# M868H.net
KiCad netlist of a schematic drawn in EAGLE
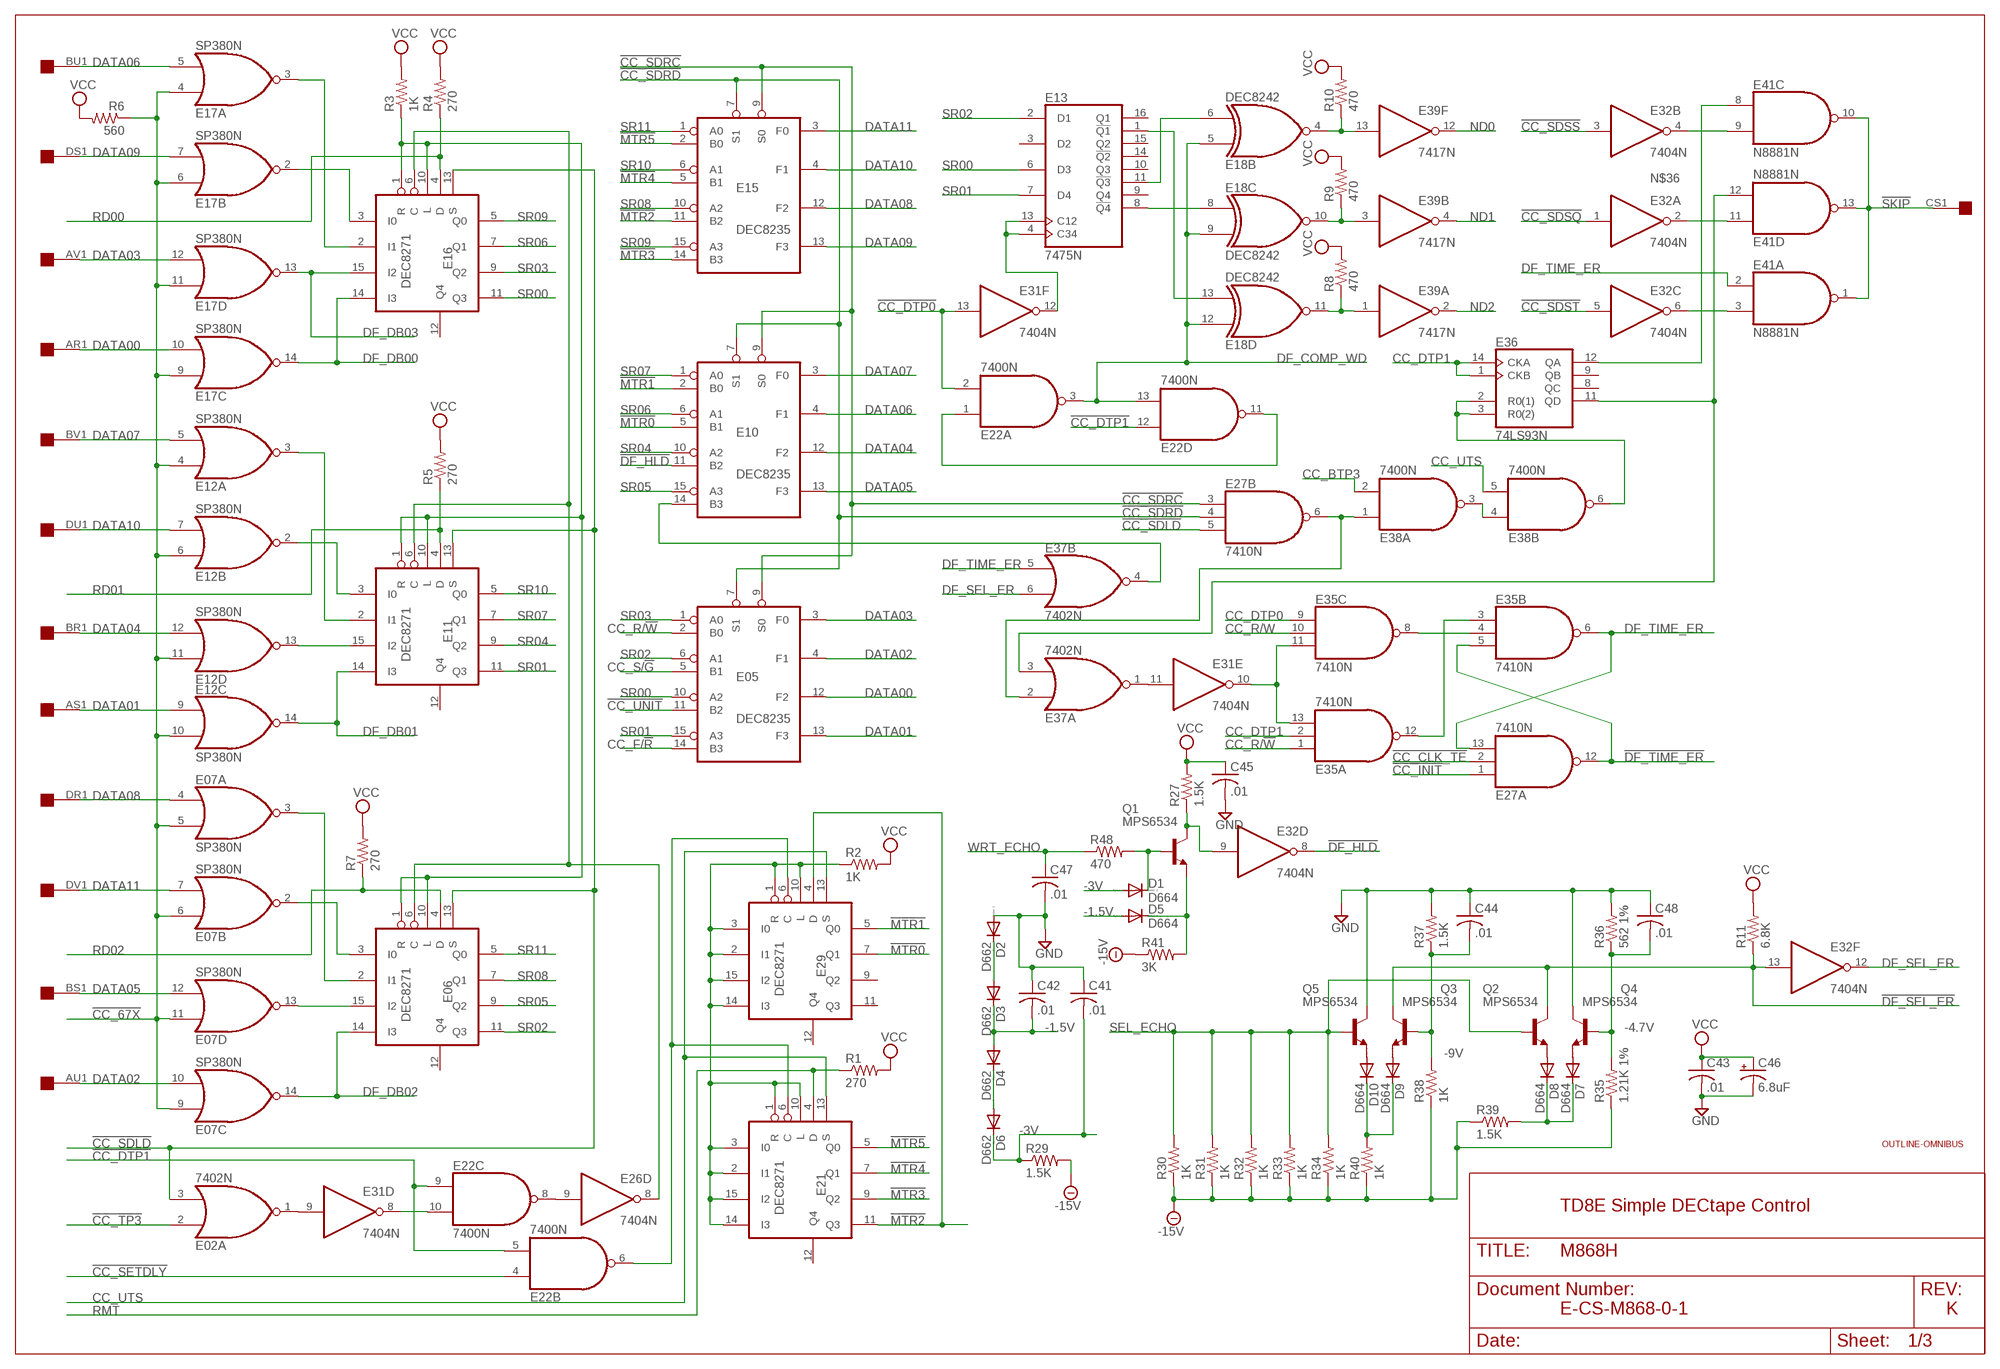
[diagram p0: schematic, sheet 1]
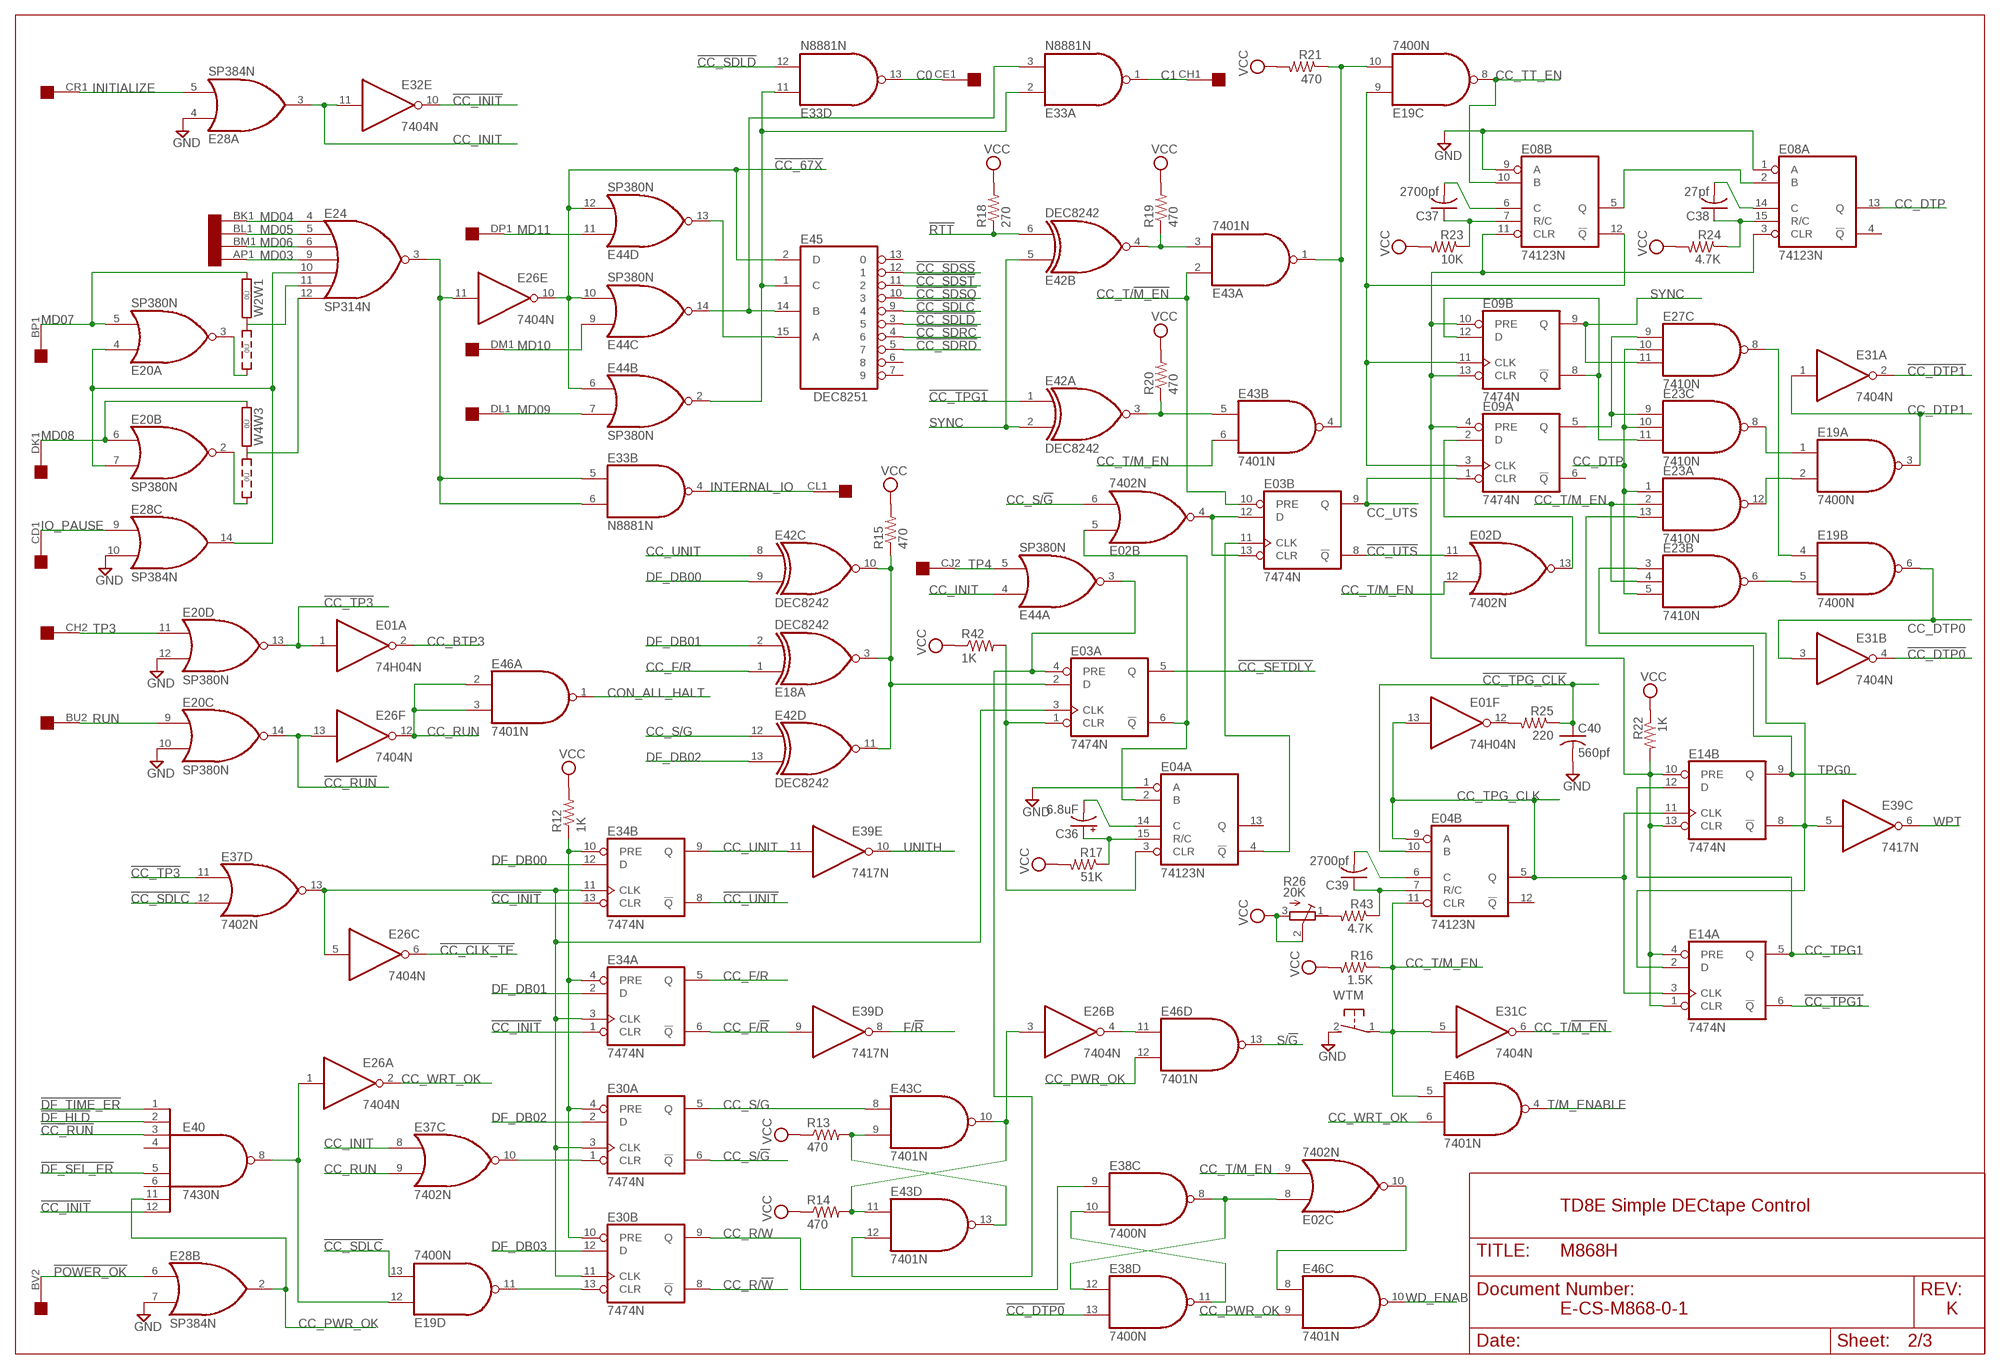
[diagram p1: schematic, sheet 2]
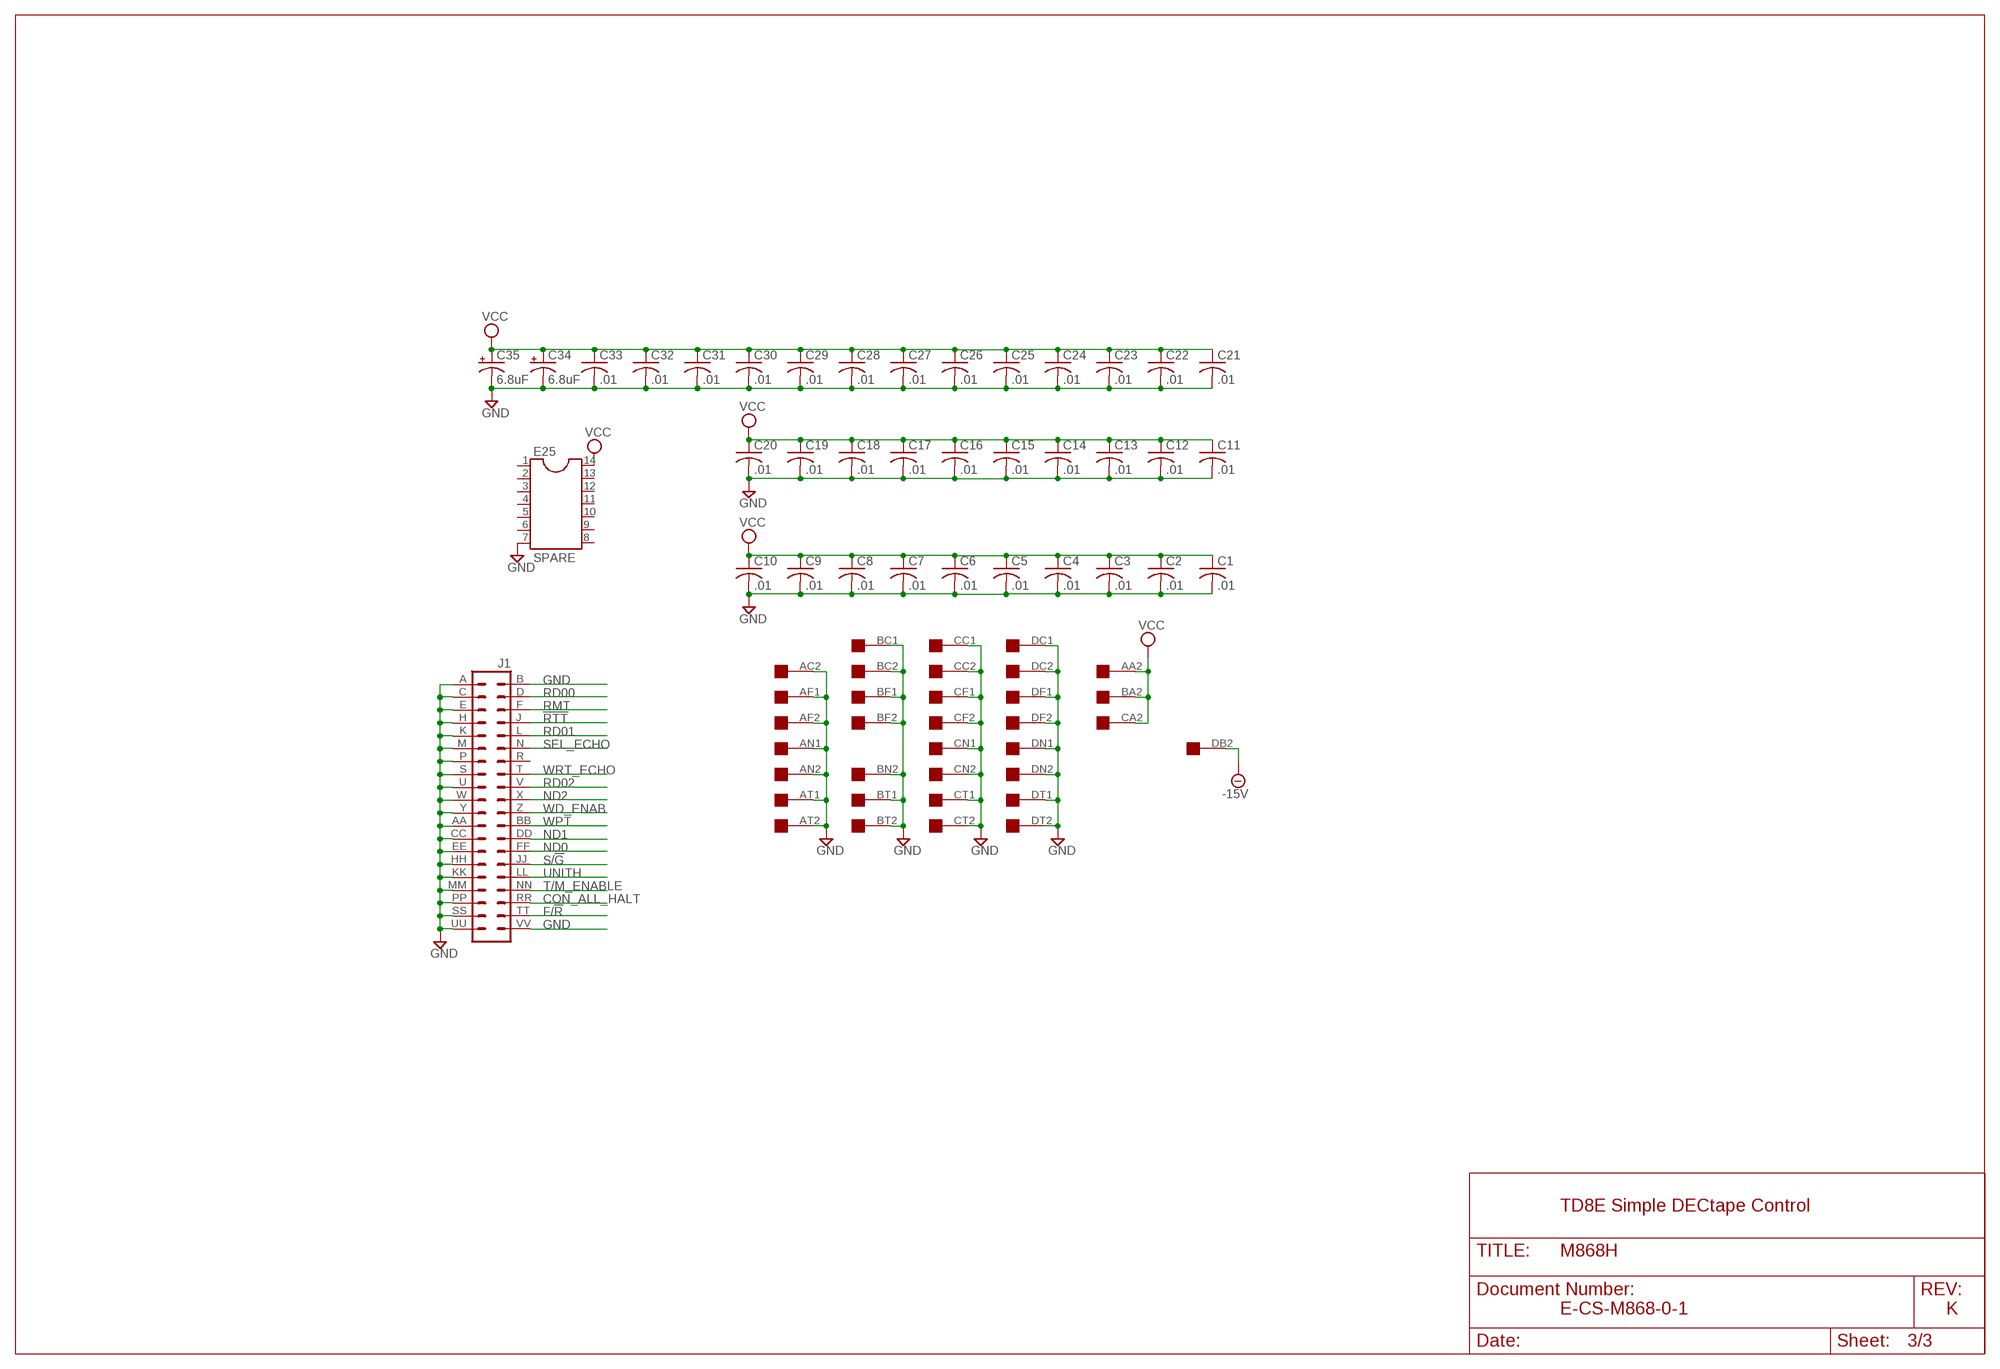
[diagram p2: schematic, sheet 3]

(export (version "E")
  (design (tool "Eeschema 10.0.6"))
  (components
    (comp (ref "C36")
      (value "6.8uF")
      (footprint "eagle-import:E12-8")
      (libsource (lib "eagle-import") (part "CPOL-USE20-8AXIAL"))
    )
    (comp (ref "C37")
      (value "2700pf")
      (footprint "eagle-import:C102-043X133")
      (libsource (lib "eagle-import") (part "C-US102-043X133"))
    )
    (comp (ref "C38")
      (value "27pf")
      (footprint "eagle-import:C050-025X075")
      (libsource (lib "eagle-import") (part "C-US050-025X075"))
    )
    (comp (ref "C39")
      (value "2700pf")
      (footprint "eagle-import:C102-043X133")
      (libsource (lib "eagle-import") (part "C-US102-043X133"))
    )
    (comp (ref "C40")
      (value "560pf")
      (footprint "eagle-import:C075-032X103")
      (libsource (lib "eagle-import") (part "C-US075-032X103"))
    )
    (comp (ref "E01")
      (value "74H04N")
      (footprint "eagle-import:DIL14")
      (libsource (lib "eagle-import") (part "7404NS"))
    )
    (comp (ref "E02")
      (value "7402N")
      (footprint "eagle-import:DIL14")
      (libsource (lib "eagle-import") (part "7402N"))
    )
    (comp (ref "E03")
      (value "7474N")
      (footprint "eagle-import:DIL14")
      (libsource (lib "eagle-import") (part "7474NS"))
    )
    (comp (ref "E04")
      (value "74123N")
      (footprint "eagle-import:DIL16")
      (libsource (lib "eagle-import") (part "74123N"))
    )
    (comp (ref "E08")
      (value "74123N")
      (footprint "eagle-import:DIL16")
      (libsource (lib "eagle-import") (part "74123N"))
    )
    (comp (ref "E09")
      (value "7474N")
      (footprint "eagle-import:DIL14")
      (libsource (lib "eagle-import") (part "7474NS"))
    )
    (comp (ref "E14")
      (value "7474N")
      (footprint "eagle-import:DIL14")
      (libsource (lib "eagle-import") (part "7474NS"))
    )
    (comp (ref "E18")
      (value "DEC8242")
      (footprint "eagle-import:DIL14")
      (libsource (lib "eagle-import") (part "74266NLS"))
    )
    (comp (ref "E19")
      (value "7400N")
      (footprint "eagle-import:DIL14")
      (libsource (lib "eagle-import") (part "7400N"))
    )
    (comp (ref "E20")
      (value "SP380N")
      (footprint "eagle-import:DIL14")
      (libsource (lib "eagle-import") (part "SP380N"))
    )
    (comp (ref "E23")
      (value "7410N")
      (footprint "eagle-import:DIL14")
      (libsource (lib "eagle-import") (part "7410N"))
    )
    (comp (ref "E24")
      (value "SP314N")
      (footprint "eagle-import:DIL14")
      (libsource (lib "eagle-import") (part "SP314N"))
    )
    (comp (ref "E26")
      (value "7404N")
      (footprint "eagle-import:DIL14")
      (libsource (lib "eagle-import") (part "7404N"))
    )
    (comp (ref "E27")
      (value "7410N")
      (footprint "eagle-import:DIL14")
      (libsource (lib "eagle-import") (part "7410N"))
    )
    (comp (ref "E28")
      (value "SP384N")
      (footprint "eagle-import:DIL14")
      (libsource (lib "eagle-import") (part "SP384N"))
    )
    (comp (ref "E30")
      (value "7474N")
      (footprint "eagle-import:DIL14")
      (libsource (lib "eagle-import") (part "7474NS"))
    )
    (comp (ref "E31")
      (value "7404N")
      (footprint "eagle-import:DIL14")
      (libsource (lib "eagle-import") (part "7404N"))
    )
    (comp (ref "E32")
      (value "7404N")
      (footprint "eagle-import:DIL14")
      (libsource (lib "eagle-import") (part "7404N"))
    )
    (comp (ref "E33")
      (value "N8881N")
      (footprint "eagle-import:DIL14")
      (libsource (lib "eagle-import") (part "N8881N"))
    )
    (comp (ref "E34")
      (value "7474N")
      (footprint "eagle-import:DIL14")
      (libsource (lib "eagle-import") (part "7474NS"))
    )
    (comp (ref "E37")
      (value "7402N")
      (footprint "eagle-import:DIL14")
      (libsource (lib "eagle-import") (part "7402N"))
    )
    (comp (ref "E38")
      (value "7400N")
      (footprint "eagle-import:DIL14")
      (libsource (lib "eagle-import") (part "7400N"))
    )
    (comp (ref "E39")
      (value "7417N")
      (footprint "eagle-import:DIL14")
      (libsource (lib "eagle-import") (part "7417N"))
    )
    (comp (ref "E40")
      (value "7430N")
      (footprint "eagle-import:DIL14")
      (libsource (lib "eagle-import") (part "7430N"))
    )
    (comp (ref "E42")
      (value "DEC8242")
      (footprint "eagle-import:DIL14")
      (libsource (lib "eagle-import") (part "74266NLS"))
    )
    (comp (ref "E43")
      (value "7401N")
      (footprint "eagle-import:DIL14")
      (libsource (lib "eagle-import") (part "7401NLS"))
    )
    (comp (ref "E44")
      (value "SP380N")
      (footprint "eagle-import:DIL14")
      (libsource (lib "eagle-import") (part "SP380N"))
    )
    (comp (ref "E45")
      (value "DEC8251")
      (footprint "eagle-import:DIL16")
      (libsource (lib "eagle-import") (part "DEC8251"))
    )
    (comp (ref "E46")
      (value "7401N")
      (footprint "eagle-import:DIL14")
      (libsource (lib "eagle-import") (part "7401NLS"))
    )
    (comp (ref "EDGE$")
      (value "QUAD")
      (footprint "eagle-import:EDGE-CON8")
      (libsource (lib "eagle-import") (part "QUAD"))
    )
    (comp (ref "R12")
      (value "1K")
      (footprint "eagle-import:0207_10")
      (libsource (lib "eagle-import") (part "R-US_0207/10"))
    )
    (comp (ref "R13")
      (value "470")
      (footprint "eagle-import:0207_10")
      (libsource (lib "eagle-import") (part "R-US_0207/10"))
    )
    (comp (ref "R14")
      (value "470")
      (footprint "eagle-import:0207_10")
      (libsource (lib "eagle-import") (part "R-US_0207/10"))
    )
    (comp (ref "R15")
      (value "470")
      (footprint "eagle-import:0207_10")
      (libsource (lib "eagle-import") (part "R-US_0207/10"))
    )
    (comp (ref "R16")
      (value "1.5K")
      (footprint "eagle-import:0207_10")
      (libsource (lib "eagle-import") (part "R-US_0207/10"))
    )
    (comp (ref "R17")
      (value "51K")
      (footprint "eagle-import:0207_10")
      (libsource (lib "eagle-import") (part "R-US_0207/10"))
    )
    (comp (ref "R18")
      (value "270")
      (footprint "eagle-import:0207_10")
      (libsource (lib "eagle-import") (part "R-US_0207/10"))
    )
    (comp (ref "R19")
      (value "470")
      (footprint "eagle-import:0207_10")
      (libsource (lib "eagle-import") (part "R-US_0207/10"))
    )
    (comp (ref "R20")
      (value "470")
      (footprint "eagle-import:0207_10")
      (libsource (lib "eagle-import") (part "R-US_0207/10"))
    )
    (comp (ref "R21")
      (value "470")
      (footprint "eagle-import:0207_10")
      (libsource (lib "eagle-import") (part "R-US_0207/10"))
    )
    (comp (ref "R22")
      (value "1K")
      (footprint "eagle-import:0207_10")
      (libsource (lib "eagle-import") (part "R-US_0207/10"))
    )
    (comp (ref "R23")
      (value "10K")
      (footprint "eagle-import:0207_10")
      (libsource (lib "eagle-import") (part "R-US_0207/10"))
    )
    (comp (ref "R24")
      (value "4.7K")
      (footprint "eagle-import:0207_10")
      (libsource (lib "eagle-import") (part "R-US_0207/10"))
    )
    (comp (ref "R25")
      (value "220")
      (footprint "eagle-import:0207_10")
      (libsource (lib "eagle-import") (part "R-US_0207/10"))
    )
    (comp (ref "R26")
      (value "20K")
      (footprint "eagle-import:3006Y")
      (libsource (lib "eagle-import") (part "275P"))
    )
    (comp (ref "R42")
      (value "1K")
      (footprint "eagle-import:0207_10")
      (libsource (lib "eagle-import") (part "R-US_0207/10"))
    )
    (comp (ref "R43")
      (value "4.7K")
      (footprint "eagle-import:0207_10")
      (libsource (lib "eagle-import") (part "R-US_0207/10"))
    )
    (comp (ref "W2W1")
      (value "0R2")
      (footprint "eagle-import:0R2_10")
      (libsource (lib "eagle-import") (part "0R2"))
    )
    (comp (ref "W4W3")
      (value "0R2")
      (footprint "eagle-import:0R2_10")
      (libsource (lib "eagle-import") (part "0R2"))
    )
    (comp (ref "WTM")
      (value "31-XX")
      (footprint "eagle-import:B3F-31XX")
      (fields (field (name "MPN") "B3F-3100"))
      (libsource (lib "eagle-import") (part "31-XX"))
    )
    (comp (ref "C1")
      (value ".01")
      (footprint "eagle-import:C050-025X075")
      (libsource (lib "eagle-import") (part "C-US050-025X075"))
    )
    (comp (ref "C2")
      (value ".01")
      (footprint "eagle-import:C050-025X075")
      (libsource (lib "eagle-import") (part "C-US050-025X075"))
    )
    (comp (ref "C3")
      (value ".01")
      (footprint "eagle-import:C050-025X075")
      (libsource (lib "eagle-import") (part "C-US050-025X075"))
    )
    (comp (ref "C4")
      (value ".01")
      (footprint "eagle-import:C050-025X075")
      (libsource (lib "eagle-import") (part "C-US050-025X075"))
    )
    (comp (ref "C5")
      (value ".01")
      (footprint "eagle-import:C050-025X075")
      (libsource (lib "eagle-import") (part "C-US050-025X075"))
    )
    (comp (ref "C6")
      (value ".01")
      (footprint "eagle-import:C050-025X075")
      (libsource (lib "eagle-import") (part "C-US050-025X075"))
    )
    (comp (ref "C7")
      (value ".01")
      (footprint "eagle-import:C050-025X075")
      (libsource (lib "eagle-import") (part "C-US050-025X075"))
    )
    (comp (ref "C8")
      (value ".01")
      (footprint "eagle-import:C050-025X075")
      (libsource (lib "eagle-import") (part "C-US050-025X075"))
    )
    (comp (ref "C9")
      (value ".01")
      (footprint "eagle-import:C050-025X075")
      (libsource (lib "eagle-import") (part "C-US050-025X075"))
    )
    (comp (ref "C10")
      (value ".01")
      (footprint "eagle-import:C050-025X075")
      (libsource (lib "eagle-import") (part "C-US050-025X075"))
    )
    (comp (ref "C11")
      (value ".01")
      (footprint "eagle-import:C050-025X075")
      (libsource (lib "eagle-import") (part "C-US050-025X075"))
    )
    (comp (ref "C12")
      (value ".01")
      (footprint "eagle-import:C050-025X075")
      (libsource (lib "eagle-import") (part "C-US050-025X075"))
    )
    (comp (ref "C13")
      (value ".01")
      (footprint "eagle-import:C050-025X075")
      (libsource (lib "eagle-import") (part "C-US050-025X075"))
    )
    (comp (ref "C14")
      (value ".01")
      (footprint "eagle-import:C050-025X075")
      (libsource (lib "eagle-import") (part "C-US050-025X075"))
    )
    (comp (ref "C15")
      (value ".01")
      (footprint "eagle-import:C050-025X075")
      (libsource (lib "eagle-import") (part "C-US050-025X075"))
    )
    (comp (ref "C16")
      (value ".01")
      (footprint "eagle-import:C050-025X075")
      (libsource (lib "eagle-import") (part "C-US050-025X075"))
    )
    (comp (ref "C17")
      (value ".01")
      (footprint "eagle-import:C050-025X075")
      (libsource (lib "eagle-import") (part "C-US050-025X075"))
    )
    (comp (ref "C18")
      (value ".01")
      (footprint "eagle-import:C050-025X075")
      (libsource (lib "eagle-import") (part "C-US050-025X075"))
    )
    (comp (ref "C19")
      (value ".01")
      (footprint "eagle-import:C050-025X075")
      (libsource (lib "eagle-import") (part "C-US050-025X075"))
    )
    (comp (ref "C20")
      (value ".01")
      (footprint "eagle-import:C050-025X075")
      (libsource (lib "eagle-import") (part "C-US050-025X075"))
    )
    (comp (ref "C21")
      (value ".01")
      (footprint "eagle-import:C050-025X075")
      (libsource (lib "eagle-import") (part "C-US050-025X075"))
    )
    (comp (ref "C22")
      (value ".01")
      (footprint "eagle-import:C050-025X075")
      (libsource (lib "eagle-import") (part "C-US050-025X075"))
    )
    (comp (ref "C23")
      (value ".01")
      (footprint "eagle-import:C050-025X075")
      (libsource (lib "eagle-import") (part "C-US050-025X075"))
    )
    (comp (ref "C24")
      (value ".01")
      (footprint "eagle-import:C050-025X075")
      (libsource (lib "eagle-import") (part "C-US050-025X075"))
    )
    (comp (ref "C25")
      (value ".01")
      (footprint "eagle-import:C050-025X075")
      (libsource (lib "eagle-import") (part "C-US050-025X075"))
    )
    (comp (ref "C26")
      (value ".01")
      (footprint "eagle-import:C050-025X075")
      (libsource (lib "eagle-import") (part "C-US050-025X075"))
    )
    (comp (ref "C27")
      (value ".01")
      (footprint "eagle-import:C050-025X075")
      (libsource (lib "eagle-import") (part "C-US050-025X075"))
    )
    (comp (ref "C28")
      (value ".01")
      (footprint "eagle-import:C050-025X075")
      (libsource (lib "eagle-import") (part "C-US050-025X075"))
    )
    (comp (ref "C29")
      (value ".01")
      (footprint "eagle-import:C050-025X075")
      (libsource (lib "eagle-import") (part "C-US050-025X075"))
    )
    (comp (ref "C30")
      (value ".01")
      (footprint "eagle-import:C050-025X075")
      (libsource (lib "eagle-import") (part "C-US050-025X075"))
    )
    (comp (ref "C31")
      (value ".01")
      (footprint "eagle-import:C050-025X075")
      (libsource (lib "eagle-import") (part "C-US050-025X075"))
    )
    (comp (ref "C32")
      (value ".01")
      (footprint "eagle-import:C050-025X075")
      (libsource (lib "eagle-import") (part "C-US050-025X075"))
    )
    (comp (ref "C33")
      (value ".01")
      (footprint "eagle-import:C050-025X075")
      (libsource (lib "eagle-import") (part "C-US050-025X075"))
    )
    (comp (ref "C34")
      (value "6.8uF")
      (footprint "eagle-import:E12-8")
      (libsource (lib "eagle-import") (part "CPOL-USE20-8AXIAL"))
    )
    (comp (ref "C35")
      (value "6.8uF")
      (footprint "eagle-import:E12-8")
      (libsource (lib "eagle-import") (part "CPOL-USE20-8AXIAL"))
    )
    (comp (ref "E25")
      (value "SPARE")
      (footprint "eagle-import:DIL14")
      (libsource (lib "eagle-import") (part "DIL14"))
    )
    (comp (ref "J1")
      (value "DEC40PINH")
      (footprint "eagle-import:DEC40PINH")
      (libsource (lib "eagle-import") (part "DEC40PINH"))
    )
    (comp (ref "C41")
      (value ".01")
      (footprint "eagle-import:C050-025X075")
      (libsource (lib "eagle-import") (part "C-US050-025X075"))
    )
    (comp (ref "C42")
      (value ".01")
      (footprint "eagle-import:C050-025X075")
      (libsource (lib "eagle-import") (part "C-US050-025X075"))
    )
    (comp (ref "C43")
      (value ".01")
      (footprint "eagle-import:C050-025X075")
      (libsource (lib "eagle-import") (part "C-US050-025X075"))
    )
    (comp (ref "C44")
      (value ".01")
      (footprint "eagle-import:C050-025X075")
      (libsource (lib "eagle-import") (part "C-US050-025X075"))
    )
    (comp (ref "C45")
      (value ".01")
      (footprint "eagle-import:C050-025X075")
      (libsource (lib "eagle-import") (part "C-US050-025X075"))
    )
    (comp (ref "C46")
      (value "6.8uF")
      (footprint "eagle-import:E12-8")
      (libsource (lib "eagle-import") (part "CPOL-USE20-8AXIAL"))
    )
    (comp (ref "C47")
      (value ".01")
      (footprint "eagle-import:C050-025X075")
      (libsource (lib "eagle-import") (part "C-US050-025X075"))
    )
    (comp (ref "C48")
      (value ".01")
      (footprint "eagle-import:C050-025X075")
      (libsource (lib "eagle-import") (part "C-US050-025X075"))
    )
    (comp (ref "D1")
      (value "D664")
      (footprint "eagle-import:DO35-10")
      (libsource (lib "eagle-import") (part "1N4148DO35-10"))
    )
    (comp (ref "D2")
      (value "D662")
      (footprint "eagle-import:DO35-10")
      (libsource (lib "eagle-import") (part "1N4148DO35-10"))
    )
    (comp (ref "D3")
      (value "D662")
      (footprint "eagle-import:DO35-10")
      (libsource (lib "eagle-import") (part "1N4148DO35-10"))
    )
    (comp (ref "D4")
      (value "D662")
      (footprint "eagle-import:DO35-10")
      (libsource (lib "eagle-import") (part "1N4148DO35-10"))
    )
    (comp (ref "D5")
      (value "D664")
      (footprint "eagle-import:DO35-10")
      (libsource (lib "eagle-import") (part "1N4148DO35-10"))
    )
    (comp (ref "D6")
      (value "D662")
      (footprint "eagle-import:DO35-10")
      (libsource (lib "eagle-import") (part "1N4148DO35-10"))
    )
    (comp (ref "D7")
      (value "D664")
      (footprint "eagle-import:DO35-10")
      (libsource (lib "eagle-import") (part "1N4148DO35-10"))
    )
    (comp (ref "D8")
      (value "D664")
      (footprint "eagle-import:DO35-10")
      (libsource (lib "eagle-import") (part "1N4148DO35-10"))
    )
    (comp (ref "D9")
      (value "D664")
      (footprint "eagle-import:DO35-10")
      (libsource (lib "eagle-import") (part "1N4148DO35-10"))
    )
    (comp (ref "D10")
      (value "D664")
      (footprint "eagle-import:DO35-10")
      (libsource (lib "eagle-import") (part "1N4148DO35-10"))
    )
    (comp (ref "E05")
      (value "DEC8235")
      (footprint "eagle-import:DIL16")
      (libsource (lib "eagle-import") (part "DEC8235"))
    )
    (comp (ref "E06")
      (value "DEC8271")
      (footprint "eagle-import:DIL16")
      (libsource (lib "eagle-import") (part "DEC8271"))
    )
    (comp (ref "E07")
      (value "SP380N")
      (footprint "eagle-import:DIL14")
      (libsource (lib "eagle-import") (part "SP380N"))
    )
    (comp (ref "E10")
      (value "DEC8235")
      (footprint "eagle-import:DIL16")
      (libsource (lib "eagle-import") (part "DEC8235"))
    )
    (comp (ref "E11")
      (value "DEC8271")
      (footprint "eagle-import:DIL16")
      (libsource (lib "eagle-import") (part "DEC8271"))
    )
    (comp (ref "E12")
      (value "SP380N")
      (footprint "eagle-import:DIL14")
      (libsource (lib "eagle-import") (part "SP380N"))
    )
    (comp (ref "E13")
      (value "7475N")
      (footprint "eagle-import:DIL16")
      (libsource (lib "eagle-import") (part "7475N"))
    )
    (comp (ref "E15")
      (value "DEC8235")
      (footprint "eagle-import:DIL16")
      (libsource (lib "eagle-import") (part "DEC8235"))
    )
    (comp (ref "E16")
      (value "DEC8271")
      (footprint "eagle-import:DIL16")
      (libsource (lib "eagle-import") (part "DEC8271"))
    )
    (comp (ref "E17")
      (value "SP380N")
      (footprint "eagle-import:DIL14")
      (libsource (lib "eagle-import") (part "SP380N"))
    )
    (comp (ref "E21")
      (value "DEC8271")
      (footprint "eagle-import:DIL16")
      (libsource (lib "eagle-import") (part "DEC8271"))
    )
    (comp (ref "E22")
      (value "7400N")
      (footprint "eagle-import:DIL14")
      (libsource (lib "eagle-import") (part "7400N"))
    )
    (comp (ref "E29")
      (value "DEC8271")
      (footprint "eagle-import:DIL16")
      (libsource (lib "eagle-import") (part "DEC8271"))
    )
    (comp (ref "E35")
      (value "7410N")
      (footprint "eagle-import:DIL14")
      (libsource (lib "eagle-import") (part "7410N"))
    )
    (comp (ref "E36")
      (value "74LS93N")
      (footprint "eagle-import:DIL14")
      (libsource (lib "eagle-import") (part "7493NLS"))
    )
    (comp (ref "E41")
      (value "N8881N")
      (footprint "eagle-import:DIL14")
      (libsource (lib "eagle-import") (part "N8881N"))
    )
    (comp (ref "Q1")
      (value "MPS6534")
      (footprint "eagle-import:TO5")
      (libsource (lib "eagle-import") (part "2N2219"))
    )
    (comp (ref "Q2")
      (value "MPS6534")
      (footprint "eagle-import:TO5")
      (libsource (lib "eagle-import") (part "2N2219"))
    )
    (comp (ref "Q3")
      (value "MPS6534")
      (footprint "eagle-import:TO5")
      (libsource (lib "eagle-import") (part "2N2219"))
    )
    (comp (ref "Q4")
      (value "MPS6534")
      (footprint "eagle-import:TO5")
      (libsource (lib "eagle-import") (part "2N2219"))
    )
    (comp (ref "Q5")
      (value "MPS6534")
      (footprint "eagle-import:TO5")
      (libsource (lib "eagle-import") (part "2N2219"))
    )
    (comp (ref "R1")
      (value "270")
      (footprint "eagle-import:0207_10")
      (libsource (lib "eagle-import") (part "R-US_0207/10"))
    )
    (comp (ref "R2")
      (value "1K")
      (footprint "eagle-import:0207_10")
      (libsource (lib "eagle-import") (part "R-US_0207/10"))
    )
    (comp (ref "R3")
      (value "1K")
      (footprint "eagle-import:0207_10")
      (libsource (lib "eagle-import") (part "R-US_0207/10"))
    )
    (comp (ref "R4")
      (value "270")
      (footprint "eagle-import:0207_10")
      (libsource (lib "eagle-import") (part "R-US_0207/10"))
    )
    (comp (ref "R5")
      (value "270")
      (footprint "eagle-import:0207_10")
      (libsource (lib "eagle-import") (part "R-US_0207/10"))
    )
    (comp (ref "R6")
      (value "560")
      (footprint "eagle-import:0207_10")
      (libsource (lib "eagle-import") (part "R-US_0207/10"))
    )
    (comp (ref "R7")
      (value "270")
      (footprint "eagle-import:0207_10")
      (libsource (lib "eagle-import") (part "R-US_0207/10"))
    )
    (comp (ref "R8")
      (value "470")
      (footprint "eagle-import:0207_10")
      (libsource (lib "eagle-import") (part "R-US_0207/10"))
    )
    (comp (ref "R9")
      (value "470")
      (footprint "eagle-import:0207_10")
      (libsource (lib "eagle-import") (part "R-US_0207/10"))
    )
    (comp (ref "R10")
      (value "470")
      (footprint "eagle-import:0207_10")
      (libsource (lib "eagle-import") (part "R-US_0207/10"))
    )
    (comp (ref "R11")
      (value "6.8K")
      (footprint "eagle-import:0207_10")
      (libsource (lib "eagle-import") (part "R-US_0207/10"))
    )
    (comp (ref "R27")
      (value "1.5K")
      (footprint "eagle-import:0207_10")
      (libsource (lib "eagle-import") (part "R-US_0207/10"))
    )
    (comp (ref "R29")
      (value "1.5K")
      (footprint "eagle-import:0207_10")
      (libsource (lib "eagle-import") (part "R-US_0207/10"))
    )
    (comp (ref "R30")
      (value "1K")
      (footprint "eagle-import:0207_10")
      (libsource (lib "eagle-import") (part "R-US_0207/10"))
    )
    (comp (ref "R31")
      (value "1K")
      (footprint "eagle-import:0207_10")
      (libsource (lib "eagle-import") (part "R-US_0207/10"))
    )
    (comp (ref "R32")
      (value "1K")
      (footprint "eagle-import:0207_10")
      (libsource (lib "eagle-import") (part "R-US_0207/10"))
    )
    (comp (ref "R33")
      (value "1K")
      (footprint "eagle-import:0207_10")
      (libsource (lib "eagle-import") (part "R-US_0207/10"))
    )
    (comp (ref "R34")
      (value "1K")
      (footprint "eagle-import:0207_10")
      (libsource (lib "eagle-import") (part "R-US_0207/10"))
    )
    (comp (ref "R35")
      (value "1.21K 1%")
      (footprint "eagle-import:0207_15")
      (libsource (lib "eagle-import") (part "R-US_0207/15"))
    )
    (comp (ref "R36")
      (value "562 1%")
      (footprint "eagle-import:0207_15")
      (libsource (lib "eagle-import") (part "R-US_0207/15"))
    )
    (comp (ref "R37")
      (value "1.5K")
      (footprint "eagle-import:0207_10")
      (libsource (lib "eagle-import") (part "R-US_0207/10"))
    )
    (comp (ref "R38")
      (value "1K")
      (footprint "eagle-import:0207_10")
      (libsource (lib "eagle-import") (part "R-US_0207/10"))
    )
    (comp (ref "R39")
      (value "1.5K")
      (footprint "eagle-import:0207_10")
      (libsource (lib "eagle-import") (part "R-US_0207/10"))
    )
    (comp (ref "R40")
      (value "1K")
      (footprint "eagle-import:0207_10")
      (libsource (lib "eagle-import") (part "R-US_0207/10"))
    )
    (comp (ref "R41")
      (value "3K")
      (footprint "eagle-import:0207_10")
      (libsource (lib "eagle-import") (part "R-US_0207/10"))
    )
    (comp (ref "R48")
      (value "470")
      (footprint "eagle-import:0207_10")
      (libsource (lib "eagle-import") (part "R-US_0207/10"))
    )
    (comp (ref "U$1")
      (value "OUTLINE-OMNIBUS")
      (footprint "eagle-import:OMNIBUS")
      (libsource (lib "eagle-import") (part "OUTLINE-OMNIBUS"))
    )
  )
  (nets
    (net (code "1") (name "-1.5V") (class "Default")
      (node (ref "C42") (pin "2") (pinfunction "2_2") (pintype "passive"))
      (node (ref "D3") (pin "C") (pinfunction "C_C") (pintype "passive"))
      (node (ref "D4") (pin "A") (pinfunction "A_A") (pintype "passive"))
      (node (ref "D5") (pin "A") (pinfunction "A_A") (pintype "passive"))
    )
    (net (code "2") (name "-3V") (class "Default")
      (node (ref "C41") (pin "2") (pinfunction "2_2") (pintype "passive"))
      (node (ref "D1") (pin "A") (pinfunction "A_A") (pintype "passive"))
      (node (ref "D6") (pin "C") (pinfunction "C_C") (pintype "passive"))
      (node (ref "R29") (pin "1") (pinfunction "1_1") (pintype "passive"))
    )
    (net (code "3") (name "-4.7V") (class "Default")
      (node (ref "C48") (pin "2") (pinfunction "2_2") (pintype "passive"))
      (node (ref "Q4") (pin "2") (pinfunction "B_2") (pintype "passive"))
      (node (ref "R35") (pin "2") (pinfunction "2_2") (pintype "passive"))
      (node (ref "R36") (pin "1") (pinfunction "1_1") (pintype "passive"))
    )
    (net (code "4") (name "-9V") (class "Default")
      (node (ref "C44") (pin "2") (pinfunction "2_2") (pintype "passive"))
      (node (ref "Q3") (pin "2") (pinfunction "B_2") (pintype "passive"))
      (node (ref "R37") (pin "1") (pinfunction "1_1") (pintype "passive"))
      (node (ref "R38") (pin "2") (pinfunction "2_2") (pintype "passive"))
    )
    (net (code "5") (name "-15V") (class "Default")
      (node (ref "EDGE$") (pin "DB2") (pinfunction "1_DB2") (pintype "bidirectional"))
      (node (ref "R29") (pin "2") (pinfunction "2_2") (pintype "passive"))
      (node (ref "R30") (pin "1") (pinfunction "1_1") (pintype "passive"))
      (node (ref "R31") (pin "1") (pinfunction "1_1") (pintype "passive"))
      (node (ref "R32") (pin "1") (pinfunction "1_1") (pintype "passive"))
      (node (ref "R33") (pin "1") (pinfunction "1_1") (pintype "passive"))
      (node (ref "R34") (pin "1") (pinfunction "1_1") (pintype "passive"))
      (node (ref "R35") (pin "1") (pinfunction "1_1") (pintype "passive"))
      (node (ref "R38") (pin "1") (pinfunction "1_1") (pintype "passive"))
      (node (ref "R39") (pin "1") (pinfunction "1_1") (pintype "passive"))
      (node (ref "R40") (pin "1") (pinfunction "1_1") (pintype "passive"))
      (node (ref "R41") (pin "1") (pinfunction "1_1") (pintype "passive"))
    )
    (net (code "6") (name "C0") (class "Default")
      (node (ref "E33") (pin "13") (pinfunction "O_13") (pintype "open_collector"))
      (node (ref "EDGE$") (pin "CE1") (pinfunction "1_CE1") (pintype "bidirectional"))
    )
    (net (code "7") (name "C1") (class "Default")
      (node (ref "E33") (pin "1") (pinfunction "O_1") (pintype "open_collector"))
      (node (ref "EDGE$") (pin "CH1") (pinfunction "1_CH1") (pintype "bidirectional"))
    )
    (net (code "8") (name "CC_BTP3") (class "Default")
      (node (ref "E01") (pin "2") (pinfunction "O_2") (pintype "output"))
      (node (ref "E38") (pin "2") (pinfunction "I1_2") (pintype "input"))
    )
    (net (code "9") (name "CC_DTP") (class "Default")
      (node (ref "E08") (pin "13") (pinfunction "Q_13") (pintype "output"))
      (node (ref "E23") (pin "1") (pinfunction "I0_1") (pintype "input"))
      (node (ref "E23") (pin "10") (pinfunction "I1_10") (pintype "input"))
      (node (ref "E23") (pin "5") (pinfunction "I2_5") (pintype "input"))
      (node (ref "E27") (pin "10") (pinfunction "I1_10") (pintype "input"))
    )
    (net (code "10") (name "CC_DTP0") (class "Default")
      (node (ref "E19") (pin "6") (pinfunction "O_6") (pintype "output"))
      (node (ref "E31") (pin "3") (pinfunction "I_3") (pintype "input"))
      (node (ref "E35") (pin "9") (pinfunction "I0_9") (pintype "input"))
    )
    (net (code "11") (name "CC_DTP1") (class "Default")
      (node (ref "E19") (pin "3") (pinfunction "O_3") (pintype "output"))
      (node (ref "E31") (pin "1") (pinfunction "I_1") (pintype "input"))
      (node (ref "E35") (pin "2") (pinfunction "I1_2") (pintype "input"))
      (node (ref "E36") (pin "1") (pinfunction "CKB_1") (pintype "input"))
      (node (ref "E36") (pin "14") (pinfunction "CKA_14") (pintype "input"))
    )
    (net (code "12") (name "CC_F{slash}R") (class "Default")
      (node (ref "E18") (pin "1") (pinfunction "I0_1") (pintype "input"))
      (node (ref "E34") (pin "5") (pinfunction "Q_5") (pintype "output"))
    )
    (net (code "13") (name "CC_F{slash}~{R}") (class "Default")
      (node (ref "E05") (pin "14") (pinfunction "B3_14") (pintype "input"))
      (node (ref "E34") (pin "6") (pinfunction "~{Q}_6") (pintype "output"))
      (node (ref "E39") (pin "9") (pinfunction "I_9") (pintype "input"))
    )
    (net (code "14") (name "CC_INIT") (class "Default")
      (node (ref "E28") (pin "3") (pinfunction "O_3") (pintype "output"))
      (node (ref "E32") (pin "11") (pinfunction "I_11") (pintype "input"))
      (node (ref "E37") (pin "8") (pinfunction "I0_8") (pintype "input"))
      (node (ref "E44") (pin "4") (pinfunction "I0_4") (pintype "input"))
    )
    (net (code "15") (name "CC_PWR_OK") (class "Default")
      (node (ref "E28") (pin "2") (pinfunction "O_2") (pintype "output"))
      (node (ref "E40") (pin "11") (pinfunction "I6_11") (pintype "input"))
      (node (ref "E46") (pin "12") (pinfunction "I1_12") (pintype "input"))
      (node (ref "E46") (pin "9") (pinfunction "I1_9") (pintype "input"))
    )
    (net (code "16") (name "CC_RUN") (class "Default")
      (node (ref "E26") (pin "12") (pinfunction "O_12") (pintype "output"))
      (node (ref "E37") (pin "9") (pinfunction "I1_9") (pintype "input"))
      (node (ref "E46") (pin "2") (pinfunction "I0_2") (pintype "input"))
      (node (ref "E46") (pin "3") (pinfunction "I1_3") (pintype "input"))
    )
    (net (code "17") (name "CC_R{slash}W") (class "Default")
      (node (ref "E30") (pin "9") (pinfunction "Q_9") (pintype "output"))
      (node (ref "E35") (pin "10") (pinfunction "I1_10") (pintype "input"))
      (node (ref "E38") (pin "9") (pinfunction "I0_9") (pintype "input"))
    )
    (net (code "18") (name "CC_R{slash}~{W}") (class "Default")
      (node (ref "E05") (pin "2") (pinfunction "B0_2") (pintype "input"))
      (node (ref "E30") (pin "8") (pinfunction "~{Q}_8") (pintype "output"))
      (node (ref "E35") (pin "1") (pinfunction "I0_1") (pintype "input"))
    )
    (net (code "19") (name "CC_S{slash}G") (class "Default")
      (node (ref "E30") (pin "5") (pinfunction "Q_5") (pintype "output"))
      (node (ref "E42") (pin "12") (pinfunction "I0_12") (pintype "input"))
      (node (ref "E43") (pin "8") (pinfunction "I0_8") (pintype "input"))
    )
    (net (code "20") (name "CC_S{slash}~{G}") (class "Default")
      (node (ref "E02") (pin "6") (pinfunction "I1_6") (pintype "input"))
      (node (ref "E05") (pin "5") (pinfunction "B1_5") (pintype "input"))
      (node (ref "E30") (pin "6") (pinfunction "~{Q}_6") (pintype "output"))
    )
    (net (code "21") (name "CC_TPG1") (class "Default")
      (node (ref "E14") (pin "12") (pinfunction "D_12") (pintype "input"))
      (node (ref "E14") (pin "5") (pinfunction "Q_5") (pintype "output"))
    )
    (net (code "22") (name "CC_TPG_CLK") (class "Default")
      (node (ref "E01") (pin "13") (pinfunction "I_13") (pintype "input"))
      (node (ref "E04") (pin "5") (pinfunction "Q_5") (pintype "output"))
      (node (ref "E04") (pin "9") (pinfunction "A_9") (pintype "input"))
      (node (ref "E14") (pin "11") (pinfunction "CLK_11") (pintype "input"))
      (node (ref "E14") (pin "3") (pinfunction "CLK_3") (pintype "input"))
    )
    (net (code "23") (name "CC_TT_EN") (class "Default")
      (node (ref "E08") (pin "10") (pinfunction "B_10") (pintype "input"))
      (node (ref "E19") (pin "8") (pinfunction "O_8") (pintype "output"))
    )
    (net (code "24") (name "CC_T{slash}M_EN") (class "Default")
      (node (ref "E02") (pin "12") (pinfunction "I1_12") (pintype "input"))
      (node (ref "E02") (pin "9") (pinfunction "I1_9") (pintype "input"))
      (node (ref "E04") (pin "11") (pinfunction "CLR_11") (pintype "input"))
      (node (ref "E23") (pin "2") (pinfunction "I1_2") (pintype "input"))
      (node (ref "E23") (pin "4") (pinfunction "I1_4") (pintype "input"))
      (node (ref "E31") (pin "5") (pinfunction "I_5") (pintype "input"))
      (node (ref "E43") (pin "6") (pinfunction "I1_6") (pintype "input"))
      (node (ref "E46") (pin "5") (pinfunction "I0_5") (pintype "input"))
      (node (ref "R16") (pin "1") (pinfunction "1_1") (pintype "passive"))
      (node (ref "WTM") (pin "1") (pinfunction "P_1") (pintype "passive"))
    )
    (net (code "25") (name "CC_T{slash}~{M_EN}") (class "Default")
      (node (ref "E03") (pin "10") (pinfunction "PRE_10") (pintype "input"))
      (node (ref "E31") (pin "6") (pinfunction "O_6") (pintype "output"))
      (node (ref "E43") (pin "2") (pinfunction "I0_2") (pintype "input"))
    )
    (net (code "26") (name "CC_UNIT") (class "Default")
      (node (ref "E34") (pin "9") (pinfunction "Q_9") (pintype "output"))
      (node (ref "E39") (pin "11") (pinfunction "I_11") (pintype "input"))
      (node (ref "E42") (pin "8") (pinfunction "I0_8") (pintype "input"))
    )
    (net (code "27") (name "CC_UTS") (class "Default")
      (node (ref "E03") (pin "9") (pinfunction "Q_9") (pintype "output"))
      (node (ref "E09") (pin "1") (pinfunction "CLR_1") (pintype "input"))
      (node (ref "E21") (pin "13") (pinfunction "S_13") (pintype "input"))
      (node (ref "E29") (pin "13") (pinfunction "S_13") (pintype "input"))
      (node (ref "E38") (pin "5") (pinfunction "I1_5") (pintype "input"))
    )
    (net (code "28") (name "CC_WRT_OK") (class "Default")
      (node (ref "E26") (pin "2") (pinfunction "O_2") (pintype "output"))
      (node (ref "E46") (pin "6") (pinfunction "I1_6") (pintype "input"))
    )
    (net (code "29") (name "CON_ALL_HALT") (class "Default")
      (node (ref "E46") (pin "1") (pinfunction "O_1") (pintype "open_collector"))
      (node (ref "J1") (pin "RR") (pinfunction "36_RR") (pintype "bidirectional"))
    )
    (net (code "30") (name "DATA00") (class "Default")
      (node (ref "E05") (pin "12") (pinfunction "F2_12") (pintype "open_collector"))
      (node (ref "E17") (pin "10") (pinfunction "I1_10") (pintype "input"))
      (node (ref "EDGE$") (pin "AR1") (pinfunction "1_AR1") (pintype "bidirectional"))
    )
    (net (code "31") (name "DATA01") (class "Default")
      (node (ref "E05") (pin "13") (pinfunction "F3_13") (pintype "open_collector"))
      (node (ref "E12") (pin "9") (pinfunction "I0_9") (pintype "input"))
      (node (ref "EDGE$") (pin "AS1") (pinfunction "1_AS1") (pintype "bidirectional"))
    )
    (net (code "32") (name "DATA02") (class "Default")
      (node (ref "E05") (pin "4") (pinfunction "F1_4") (pintype "open_collector"))
      (node (ref "E07") (pin "10") (pinfunction "I1_10") (pintype "input"))
      (node (ref "EDGE$") (pin "AU1") (pinfunction "1_AU1") (pintype "bidirectional"))
    )
    (net (code "33") (name "DATA03") (class "Default")
      (node (ref "E05") (pin "3") (pinfunction "F0_3") (pintype "open_collector"))
      (node (ref "E17") (pin "12") (pinfunction "I1_12") (pintype "input"))
      (node (ref "EDGE$") (pin "AV1") (pinfunction "1_AV1") (pintype "bidirectional"))
    )
    (net (code "34") (name "DATA04") (class "Default")
      (node (ref "E10") (pin "12") (pinfunction "F2_12") (pintype "open_collector"))
      (node (ref "E12") (pin "12") (pinfunction "I1_12") (pintype "input"))
      (node (ref "EDGE$") (pin "BR1") (pinfunction "1_BR1") (pintype "bidirectional"))
    )
    (net (code "35") (name "DATA05") (class "Default")
      (node (ref "E07") (pin "12") (pinfunction "I1_12") (pintype "input"))
      (node (ref "E10") (pin "13") (pinfunction "F3_13") (pintype "open_collector"))
      (node (ref "EDGE$") (pin "BS1") (pinfunction "1_BS1") (pintype "bidirectional"))
    )
    (net (code "36") (name "DATA06") (class "Default")
      (node (ref "E10") (pin "4") (pinfunction "F1_4") (pintype "open_collector"))
      (node (ref "E17") (pin "5") (pinfunction "I1_5") (pintype "input"))
      (node (ref "EDGE$") (pin "BU1") (pinfunction "1_BU1") (pintype "bidirectional"))
    )
    (net (code "37") (name "DATA07") (class "Default")
      (node (ref "E10") (pin "3") (pinfunction "F0_3") (pintype "open_collector"))
      (node (ref "E12") (pin "5") (pinfunction "I1_5") (pintype "input"))
      (node (ref "EDGE$") (pin "BV1") (pinfunction "1_BV1") (pintype "bidirectional"))
    )
    (net (code "38") (name "DATA08") (class "Default")
      (node (ref "E07") (pin "4") (pinfunction "I0_4") (pintype "input"))
      (node (ref "E15") (pin "12") (pinfunction "F2_12") (pintype "open_collector"))
      (node (ref "EDGE$") (pin "DR1") (pinfunction "1_DR1") (pintype "bidirectional"))
    )
    (net (code "39") (name "DATA09") (class "Default")
      (node (ref "E15") (pin "13") (pinfunction "F3_13") (pintype "open_collector"))
      (node (ref "E17") (pin "7") (pinfunction "I1_7") (pintype "input"))
      (node (ref "EDGE$") (pin "DS1") (pinfunction "1_DS1") (pintype "bidirectional"))
    )
    (net (code "40") (name "DATA10") (class "Default")
      (node (ref "E12") (pin "7") (pinfunction "I1_7") (pintype "input"))
      (node (ref "E15") (pin "4") (pinfunction "F1_4") (pintype "open_collector"))
      (node (ref "EDGE$") (pin "DU1") (pinfunction "1_DU1") (pintype "bidirectional"))
    )
    (net (code "41") (name "DATA11") (class "Default")
      (node (ref "E07") (pin "7") (pinfunction "I1_7") (pintype "input"))
      (node (ref "E15") (pin "3") (pinfunction "F0_3") (pintype "open_collector"))
      (node (ref "EDGE$") (pin "DV1") (pinfunction "1_DV1") (pintype "bidirectional"))
    )
    (net (code "42") (name "DF_COMP_WD") (class "Default")
      (node (ref "E18") (pin "12") (pinfunction "I0_12") (pintype "input"))
      (node (ref "E18") (pin "5") (pinfunction "I0_5") (pintype "input"))
      (node (ref "E18") (pin "9") (pinfunction "I1_9") (pintype "input"))
      (node (ref "E22") (pin "13") (pinfunction "I1_13") (pintype "input"))
      (node (ref "E22") (pin "3") (pinfunction "O_3") (pintype "output"))
    )
    (net (code "43") (name "DF_DB00") (class "Default")
      (node (ref "E16") (pin "14") (pinfunction "I3_14") (pintype "input"))
      (node (ref "E17") (pin "14") (pinfunction "O_14") (pintype "output"))
      (node (ref "E34") (pin "12") (pinfunction "D_12") (pintype "input"))
      (node (ref "E42") (pin "9") (pinfunction "I1_9") (pintype "input"))
    )
    (net (code "44") (name "DF_DB01") (class "Default")
      (node (ref "E11") (pin "14") (pinfunction "I3_14") (pintype "input"))
      (node (ref "E12") (pin "14") (pinfunction "O_14") (pintype "output"))
      (node (ref "E18") (pin "2") (pinfunction "I1_2") (pintype "input"))
      (node (ref "E34") (pin "2") (pinfunction "D_2") (pintype "input"))
    )
    (net (code "45") (name "DF_DB02") (class "Default")
      (node (ref "E06") (pin "14") (pinfunction "I3_14") (pintype "input"))
      (node (ref "E07") (pin "14") (pinfunction "O_14") (pintype "output"))
      (node (ref "E30") (pin "2") (pinfunction "D_2") (pintype "input"))
      (node (ref "E42") (pin "13") (pinfunction "I1_13") (pintype "input"))
    )
    (net (code "46") (name "DF_DB03") (class "Default")
      (node (ref "E16") (pin "15") (pinfunction "I2_15") (pintype "input"))
      (node (ref "E17") (pin "13") (pinfunction "O_13") (pintype "output"))
      (node (ref "E30") (pin "12") (pinfunction "D_12") (pintype "input"))
    )
    (net (code "47") (name "DF_SEL_ER") (class "Default")
      (node (ref "E32") (pin "12") (pinfunction "O_12") (pintype "output"))
      (node (ref "E37") (pin "6") (pinfunction "I1_6") (pintype "input"))
    )
    (net (code "48") (name "DF_TIME_ER") (class "Default")
      (node (ref "E27") (pin "13") (pinfunction "I2_13") (pintype "input"))
      (node (ref "E35") (pin "6") (pinfunction "O_6") (pintype "output"))
      (node (ref "E37") (pin "5") (pinfunction "I0_5") (pintype "input"))
      (node (ref "E41") (pin "2") (pinfunction "I0_2") (pintype "input"))
    )
    (net (code "49") (name "F{slash}~{R}") (class "Default")
      (node (ref "E39") (pin "8") (pinfunction "O_8") (pintype "open_collector"))
      (node (ref "J1") (pin "TT") (pinfunction "38_TT") (pintype "bidirectional"))
    )
    (net (code "50") (name "GND") (class "Default")
      (node (ref "C1") (pin "2") (pinfunction "2_2") (pintype "passive"))
      (node (ref "C10") (pin "2") (pinfunction "2_2") (pintype "passive"))
      (node (ref "C11") (pin "2") (pinfunction "2_2") (pintype "passive"))
      (node (ref "C12") (pin "2") (pinfunction "2_2") (pintype "passive"))
      (node (ref "C13") (pin "2") (pinfunction "2_2") (pintype "passive"))
      (node (ref "C14") (pin "2") (pinfunction "2_2") (pintype "passive"))
      (node (ref "C15") (pin "2") (pinfunction "2_2") (pintype "passive"))
      (node (ref "C16") (pin "2") (pinfunction "2_2") (pintype "passive"))
      (node (ref "C17") (pin "2") (pinfunction "2_2") (pintype "passive"))
      (node (ref "C18") (pin "2") (pinfunction "2_2") (pintype "passive"))
      (node (ref "C19") (pin "2") (pinfunction "2_2") (pintype "passive"))
      (node (ref "C2") (pin "2") (pinfunction "2_2") (pintype "passive"))
      (node (ref "C20") (pin "2") (pinfunction "2_2") (pintype "passive"))
      (node (ref "C21") (pin "2") (pinfunction "2_2") (pintype "passive"))
      (node (ref "C22") (pin "2") (pinfunction "2_2") (pintype "passive"))
      (node (ref "C23") (pin "2") (pinfunction "2_2") (pintype "passive"))
      (node (ref "C24") (pin "2") (pinfunction "2_2") (pintype "passive"))
      (node (ref "C25") (pin "2") (pinfunction "2_2") (pintype "passive"))
      (node (ref "C26") (pin "2") (pinfunction "2_2") (pintype "passive"))
      (node (ref "C27") (pin "2") (pinfunction "2_2") (pintype "passive"))
      (node (ref "C28") (pin "2") (pinfunction "2_2") (pintype "passive"))
      (node (ref "C29") (pin "2") (pinfunction "2_2") (pintype "passive"))
      (node (ref "C3") (pin "2") (pinfunction "2_2") (pintype "passive"))
      (node (ref "C30") (pin "2") (pinfunction "2_2") (pintype "passive"))
      (node (ref "C31") (pin "2") (pinfunction "2_2") (pintype "passive"))
      (node (ref "C32") (pin "2") (pinfunction "2_2") (pintype "passive"))
      (node (ref "C33") (pin "2") (pinfunction "2_2") (pintype "passive"))
      (node (ref "C34") (pin "-") (pinfunction "-_-") (pintype "passive"))
      (node (ref "C35") (pin "-") (pinfunction "-_-") (pintype "passive"))
      (node (ref "C4") (pin "2") (pinfunction "2_2") (pintype "passive"))
      (node (ref "C40") (pin "2") (pinfunction "2_2") (pintype "passive"))
      (node (ref "C41") (pin "1") (pinfunction "1_1") (pintype "passive"))
      (node (ref "C42") (pin "1") (pinfunction "1_1") (pintype "passive"))
      (node (ref "C43") (pin "2") (pinfunction "2_2") (pintype "passive"))
      (node (ref "C44") (pin "1") (pinfunction "1_1") (pintype "passive"))
      (node (ref "C45") (pin "2") (pinfunction "2_2") (pintype "passive"))
      (node (ref "C46") (pin "-") (pinfunction "-_-") (pintype "passive"))
      (node (ref "C47") (pin "2") (pinfunction "2_2") (pintype "passive"))
      (node (ref "C48") (pin "1") (pinfunction "1_1") (pintype "passive"))
      (node (ref "C5") (pin "2") (pinfunction "2_2") (pintype "passive"))
      (node (ref "C6") (pin "2") (pinfunction "2_2") (pintype "passive"))
      (node (ref "C7") (pin "2") (pinfunction "2_2") (pintype "passive"))
      (node (ref "C8") (pin "2") (pinfunction "2_2") (pintype "passive"))
      (node (ref "C9") (pin "2") (pinfunction "2_2") (pintype "passive"))
      (node (ref "D2") (pin "A") (pinfunction "A_A") (pintype "passive"))
      (node (ref "E04") (pin "1") (pinfunction "A_1") (pintype "input"))
      (node (ref "E08") (pin "1") (pinfunction "A_1") (pintype "input"))
      (node (ref "E08") (pin "9") (pinfunction "A_9") (pintype "input"))
      (node (ref "E20") (pin "10") (pinfunction "I1_10") (pintype "input"))
      (node (ref "E20") (pin "12") (pinfunction "I1_12") (pintype "input"))
      (node (ref "E25") (pin "7") (pinfunction "7_7") (pintype "passive"))
      (node (ref "E28") (pin "10") (pinfunction "I1_10") (pintype "input"))
      (node (ref "E28") (pin "4") (pinfunction "I0_4") (pintype "input"))
      (node (ref "E28") (pin "7") (pinfunction "I1_7") (pintype "input"))
      (node (ref "EDGE$") (pin "AC2") (pinfunction "1_AC2") (pintype "bidirectional"))
      (node (ref "EDGE$") (pin "AF1") (pinfunction "1_AF1") (pintype "bidirectional"))
      (node (ref "EDGE$") (pin "AF2") (pinfunction "1_AF2") (pintype "bidirectional"))
      (node (ref "EDGE$") (pin "AN1") (pinfunction "1_AN1") (pintype "bidirectional"))
      (node (ref "EDGE$") (pin "AN2") (pinfunction "1_AN2") (pintype "bidirectional"))
      (node (ref "EDGE$") (pin "AT1") (pinfunction "1_AT1") (pintype "bidirectional"))
      (node (ref "EDGE$") (pin "AT2") (pinfunction "1_AT2") (pintype "bidirectional"))
      (node (ref "EDGE$") (pin "BC1") (pinfunction "1_BC1") (pintype "bidirectional"))
      (node (ref "EDGE$") (pin "BC2") (pinfunction "1_BC2") (pintype "bidirectional"))
      (node (ref "EDGE$") (pin "BF1") (pinfunction "1_BF1") (pintype "bidirectional"))
      (node (ref "EDGE$") (pin "BF2") (pinfunction "1_BF2") (pintype "bidirectional"))
      (node (ref "EDGE$") (pin "BN2") (pinfunction "1_BN2") (pintype "bidirectional"))
      (node (ref "EDGE$") (pin "BT1") (pinfunction "1_BT1") (pintype "bidirectional"))
      (node (ref "EDGE$") (pin "BT2") (pinfunction "1_BT2") (pintype "bidirectional"))
      (node (ref "EDGE$") (pin "CC1") (pinfunction "1_CC1") (pintype "bidirectional"))
      (node (ref "EDGE$") (pin "CC2") (pinfunction "1_CC2") (pintype "bidirectional"))
      (node (ref "EDGE$") (pin "CF1") (pinfunction "1_CF1") (pintype "bidirectional"))
      (node (ref "EDGE$") (pin "CF2") (pinfunction "1_CF2") (pintype "bidirectional"))
      (node (ref "EDGE$") (pin "CN1") (pinfunction "1_CN1") (pintype "bidirectional"))
      (node (ref "EDGE$") (pin "CN2") (pinfunction "1_CN2") (pintype "bidirectional"))
      (node (ref "EDGE$") (pin "CT1") (pinfunction "1_CT1") (pintype "bidirectional"))
      (node (ref "EDGE$") (pin "CT2") (pinfunction "1_CT2") (pintype "bidirectional"))
      (node (ref "EDGE$") (pin "DC1") (pinfunction "1_DC1") (pintype "bidirectional"))
      (node (ref "EDGE$") (pin "DC2") (pinfunction "1_DC2") (pintype "bidirectional"))
      (node (ref "EDGE$") (pin "DF1") (pinfunction "1_DF1") (pintype "bidirectional"))
      (node (ref "EDGE$") (pin "DF2") (pinfunction "1_DF2") (pintype "bidirectional"))
      (node (ref "EDGE$") (pin "DN1") (pinfunction "1_DN1") (pintype "bidirectional"))
      (node (ref "EDGE$") (pin "DN2") (pinfunction "1_DN2") (pintype "bidirectional"))
      (node (ref "EDGE$") (pin "DT1") (pinfunction "1_DT1") (pintype "bidirectional"))
      (node (ref "EDGE$") (pin "DT2") (pinfunction "1_DT2") (pintype "bidirectional"))
      (node (ref "J1") (pin "A") (pinfunction "1_A") (pintype "bidirectional"))
      (node (ref "J1") (pin "AA") (pinfunction "23_AA") (pintype "bidirectional"))
      (node (ref "J1") (pin "B") (pinfunction "2_B") (pintype "bidirectional"))
      (node (ref "J1") (pin "C") (pinfunction "3_C") (pintype "bidirectional"))
      (node (ref "J1") (pin "CC") (pinfunction "25_CC") (pintype "bidirectional"))
      (node (ref "J1") (pin "E") (pinfunction "5_E") (pintype "bidirectional"))
      (node (ref "J1") (pin "EE") (pinfunction "27_EE") (pintype "bidirectional"))
      (node (ref "J1") (pin "H") (pinfunction "7_H") (pintype "bidirectional"))
      (node (ref "J1") (pin "HH") (pinfunction "29_HH") (pintype "bidirectional"))
      (node (ref "J1") (pin "K") (pinfunction "9_K") (pintype "bidirectional"))
      (node (ref "J1") (pin "KK") (pinfunction "31_KK") (pintype "bidirectional"))
      (node (ref "J1") (pin "M") (pinfunction "11_M") (pintype "bidirectional"))
      (node (ref "J1") (pin "MM") (pinfunction "33_MM") (pintype "bidirectional"))
      (node (ref "J1") (pin "P") (pinfunction "13_P") (pintype "bidirectional"))
      (node (ref "J1") (pin "PP") (pinfunction "35_PP") (pintype "bidirectional"))
      (node (ref "J1") (pin "S") (pinfunction "15_S") (pintype "bidirectional"))
      (node (ref "J1") (pin "SS") (pinfunction "37_SS") (pintype "bidirectional"))
      (node (ref "J1") (pin "U") (pinfunction "17_U") (pintype "bidirectional"))
      (node (ref "J1") (pin "UU") (pinfunction "39_UU") (pintype "bidirectional"))
      (node (ref "J1") (pin "VV") (pinfunction "40_VV") (pintype "bidirectional"))
      (node (ref "J1") (pin "W") (pinfunction "19_W") (pintype "bidirectional"))
      (node (ref "J1") (pin "Y") (pinfunction "21_Y") (pintype "bidirectional"))
      (node (ref "Q4") (pin "3") (pinfunction "C_3") (pintype "passive"))
      (node (ref "Q5") (pin "3") (pinfunction "C_3") (pintype "passive"))
      (node (ref "R36") (pin "2") (pinfunction "2_2") (pintype "passive"))
      (node (ref "R37") (pin "2") (pinfunction "2_2") (pintype "passive"))
      (node (ref "WTM") (pin "2") (pinfunction "S_2") (pintype "passive"))
    )
    (net (code "51") (name "INITIALIZE") (class "Default")
      (node (ref "E28") (pin "5") (pinfunction "I1_5") (pintype "input"))
      (node (ref "EDGE$") (pin "CR1") (pinfunction "1_CR1") (pintype "bidirectional"))
    )
    (net (code "52") (name "INTERNAL_IO") (class "Default")
      (node (ref "E33") (pin "4") (pinfunction "O_4") (pintype "open_collector"))
      (node (ref "EDGE$") (pin "CL1") (pinfunction "1_CL1") (pintype "bidirectional"))
    )
    (net (code "53") (name "IO_PAUSE") (class "Default")
      (node (ref "E28") (pin "9") (pinfunction "I0_9") (pintype "input"))
      (node (ref "EDGE$") (pin "CD1") (pinfunction "1_CD1") (pintype "bidirectional"))
    )
    (net (code "54") (name "MD03") (class "Default")
      (node (ref "E24") (pin "9") (pinfunction "I3_9") (pintype "input"))
      (node (ref "EDGE$") (pin "AP1") (pinfunction "1_AP1") (pintype "bidirectional"))
    )
    (net (code "55") (name "MD04") (class "Default")
      (node (ref "E24") (pin "4") (pinfunction "I0_4") (pintype "input"))
      (node (ref "EDGE$") (pin "BK1") (pinfunction "1_BK1") (pintype "bidirectional"))
    )
    (net (code "56") (name "MD05") (class "Default")
      (node (ref "E24") (pin "5") (pinfunction "I1_5") (pintype "input"))
      (node (ref "EDGE$") (pin "BL1") (pinfunction "1_BL1") (pintype "bidirectional"))
    )
    (net (code "57") (name "MD06") (class "Default")
      (node (ref "E24") (pin "6") (pinfunction "I2_6") (pintype "input"))
      (node (ref "EDGE$") (pin "BM1") (pinfunction "1_BM1") (pintype "bidirectional"))
    )
    (net (code "58") (name "MD07") (class "Default")
      (node (ref "E20") (pin "5") (pinfunction "I1_5") (pintype "input"))
      (node (ref "EDGE$") (pin "BP1") (pinfunction "1_BP1") (pintype "bidirectional"))
      (node (ref "W2W1") (pin "1") (pinfunction "1_1") (pintype "passive"))
    )
    (net (code "59") (name "MD08") (class "Default")
      (node (ref "E20") (pin "6") (pinfunction "I0_6") (pintype "input"))
      (node (ref "EDGE$") (pin "DK1") (pinfunction "1_DK1") (pintype "bidirectional"))
      (node (ref "W4W3") (pin "1") (pinfunction "1_1") (pintype "passive"))
    )
    (net (code "60") (name "MD09") (class "Default")
      (node (ref "E44") (pin "7") (pinfunction "I1_7") (pintype "input"))
      (node (ref "EDGE$") (pin "DL1") (pinfunction "1_DL1") (pintype "bidirectional"))
    )
    (net (code "61") (name "MD10") (class "Default")
      (node (ref "E44") (pin "9") (pinfunction "I0_9") (pintype "input"))
      (node (ref "EDGE$") (pin "DM1") (pinfunction "1_DM1") (pintype "bidirectional"))
    )
    (net (code "62") (name "MD11") (class "Default")
      (node (ref "E44") (pin "11") (pinfunction "I0_11") (pintype "input"))
      (node (ref "EDGE$") (pin "DP1") (pinfunction "1_DP1") (pintype "bidirectional"))
    )
    (net (code "63") (name "N$36") (class "Default")
      (node (ref "E36") (pin "11") (pinfunction "QD_11") (pintype "output"))
      (node (ref "E37") (pin "3") (pinfunction "I1_3") (pintype "input"))
      (node (ref "E41") (pin "12") (pinfunction "I1_12") (pintype "input"))
    )
    (net (code "64") (name "ND0") (class "Default")
      (node (ref "E39") (pin "12") (pinfunction "O_12") (pintype "open_collector"))
      (node (ref "J1") (pin "FF") (pinfunction "28_FF") (pintype "bidirectional"))
    )
    (net (code "65") (name "ND1") (class "Default")
      (node (ref "E39") (pin "4") (pinfunction "O_4") (pintype "open_collector"))
      (node (ref "J1") (pin "DD") (pinfunction "26_DD") (pintype "bidirectional"))
    )
    (net (code "66") (name "ND2") (class "Default")
      (node (ref "E39") (pin "2") (pinfunction "O_2") (pintype "open_collector"))
      (node (ref "J1") (pin "X") (pinfunction "20_X") (pintype "bidirectional"))
    )
    (net (code "67") (name "Net-(D2-PadC)") (class "Default")
      (node (ref "D2") (pin "C") (pinfunction "C_C") (pintype "passive"))
      (node (ref "D3") (pin "A") (pinfunction "A_A") (pintype "passive"))
    )
    (net (code "68") (name "Net-(D4-PadC)") (class "Default")
      (node (ref "D4") (pin "C") (pinfunction "C_C") (pintype "passive"))
      (node (ref "D6") (pin "A") (pinfunction "A_A") (pintype "passive"))
    )
    (net (code "69") (name "Net-(D7-PadC)") (class "Default")
      (node (ref "D7") (pin "C") (pinfunction "C_C") (pintype "passive"))
      (node (ref "D8") (pin "C") (pinfunction "C_C") (pintype "passive"))
      (node (ref "R39") (pin "2") (pinfunction "2_2") (pintype "passive"))
    )
    (net (code "70") (name "Net-(D10-PadC)") (class "Default")
      (node (ref "D10") (pin "C") (pinfunction "C_C") (pintype "passive"))
      (node (ref "D9") (pin "C") (pinfunction "C_C") (pintype "passive"))
      (node (ref "R40") (pin "2") (pinfunction "2_2") (pintype "passive"))
    )
    (net (code "71") (name "Net-(E01F-O)") (class "Default")
      (node (ref "E01") (pin "12") (pinfunction "O_12") (pintype "output"))
      (node (ref "R25") (pin "2") (pinfunction "2_2") (pintype "passive"))
    )
    (net (code "72") (name "Net-(E02A-O)") (class "Default")
      (node (ref "E02") (pin "1") (pinfunction "O_1") (pintype "output"))
      (node (ref "E31") (pin "9") (pinfunction "I_9") (pintype "input"))
    )
    (net (code "73") (name "Net-(E02B-I0)") (class "Default")
      (node (ref "E02") (pin "5") (pinfunction "I0_5") (pintype "input"))
      (node (ref "E03") (pin "6") (pinfunction "~{Q}_6") (pintype "output"))
      (node (ref "E04") (pin "2") (pinfunction "B_2") (pintype "input"))
    )
    (net (code "74") (name "Net-(E02B-O)") (class "Default")
      (node (ref "E02") (pin "4") (pinfunction "O_4") (pintype "output"))
      (node (ref "E03") (pin "12") (pinfunction "D_12") (pintype "input"))
      (node (ref "E03") (pin "13") (pinfunction "CLR_13") (pintype "input"))
    )
    (net (code "75") (name "Net-(E02C-I0)") (class "Default")
      (node (ref "E02") (pin "8") (pinfunction "I0_8") (pintype "input"))
      (node (ref "E38") (pin "12") (pinfunction "I0_12") (pintype "input"))
      (node (ref "E38") (pin "8") (pinfunction "O_8") (pintype "output"))
    )
    (net (code "76") (name "Net-(E02C-O)") (class "Default")
      (node (ref "E02") (pin "10") (pinfunction "O_10") (pintype "output"))
      (node (ref "E46") (pin "8") (pinfunction "I0_8") (pintype "input"))
    )
    (net (code "77") (name "Net-(E02D-O)") (class "Default")
      (node (ref "E02") (pin "13") (pinfunction "O_13") (pintype "output"))
      (node (ref "E09") (pin "2") (pinfunction "D_2") (pintype "input"))
    )
    (net (code "78") (name "Net-(E03A-CLK)") (class "Default")
      (node (ref "E03") (pin "3") (pinfunction "CLK_3") (pintype "input"))
      (node (ref "E26") (pin "5") (pinfunction "I_5") (pintype "input"))
      (node (ref "E30") (pin "11") (pinfunction "CLK_11") (pintype "input"))
      (node (ref "E30") (pin "3") (pinfunction "CLK_3") (pintype "input"))
      (node (ref "E34") (pin "11") (pinfunction "CLK_11") (pintype "input"))
      (node (ref "E34") (pin "3") (pinfunction "CLK_3") (pintype "input"))
      (node (ref "E37") (pin "13") (pinfunction "O_13") (pintype "output"))
    )
    (net (code "79") (name "Net-(E03A-CLR)") (class "Default")
      (node (ref "E03") (pin "1") (pinfunction "CLR_1") (pintype "input"))
      (node (ref "E04") (pin "3") (pinfunction "CLR_3") (pintype "input"))
      (node (ref "R42") (pin "2") (pinfunction "2_2") (pintype "passive"))
    )
    (net (code "80") (name "Net-(E03A-D)") (class "Default")
      (node (ref "E03") (pin "2") (pinfunction "D_2") (pintype "input"))
      (node (ref "E18") (pin "3") (pinfunction "O_3") (pintype "open_collector"))
      (node (ref "E42") (pin "10") (pinfunction "O_10") (pintype "open_collector"))
      (node (ref "E42") (pin "11") (pinfunction "O_11") (pintype "open_collector"))
      (node (ref "R15") (pin "1") (pinfunction "1_1") (pintype "passive"))
    )
    (net (code "81") (name "Net-(E03A-PRE)") (class "Default")
      (node (ref "E03") (pin "4") (pinfunction "PRE_4") (pintype "input"))
      (node (ref "E43") (pin "12") (pinfunction "I1_12") (pintype "input"))
      (node (ref "E44") (pin "3") (pinfunction "O_3") (pintype "output"))
    )
    (net (code "82") (name "Net-(E03B-CLK)") (class "Default")
      (node (ref "E03") (pin "11") (pinfunction "CLK_11") (pintype "input"))
      (node (ref "E04") (pin "4") (pinfunction "~{Q}_4") (pintype "output"))
    )
    (net (code "83") (name "Net-(E04A-C)") (class "Default")
      (node (ref "C36") (pin "-") (pinfunction "-_-") (pintype "passive"))
      (node (ref "E04") (pin "14") (pinfunction "C_14") (pintype "input"))
    )
    (net (code "84") (name "Net-(E04A-R{slash}C)") (class "Default")
      (node (ref "C36") (pin "+") (pinfunction "+_+") (pintype "passive"))
      (node (ref "E04") (pin "15") (pinfunction "R/C_15") (pintype "input"))
      (node (ref "R17") (pin "1") (pinfunction "1_1") (pintype "passive"))
    )
    (net (code "85") (name "Net-(E04B-C)") (class "Default")
      (node (ref "C39") (pin "2") (pinfunction "2_2") (pintype "passive"))
      (node (ref "E04") (pin "6") (pinfunction "C_6") (pintype "input"))
    )
    (net (code "86") (name "Net-(E04B-R{slash}C)") (class "Default")
      (node (ref "C39") (pin "1") (pinfunction "1_1") (pintype "passive"))
      (node (ref "E04") (pin "7") (pinfunction "R/C_7") (pintype "input"))
      (node (ref "R43") (pin "1") (pinfunction "1_1") (pintype "passive"))
    )
    (net (code "87") (name "Net-(E06A-C)") (class "Default")
      (node (ref "E06") (pin "6") (pinfunction "C_6") (pintype "input"))
      (node (ref "E11") (pin "6") (pinfunction "C_6") (pintype "input"))
      (node (ref "E16") (pin "6") (pinfunction "C_6") (pintype "input"))
      (node (ref "E26") (pin "8") (pinfunction "O_8") (pintype "output"))
    )
    (net (code "88") (name "Net-(E06A-I0)") (class "Default")
      (node (ref "E06") (pin "3") (pinfunction "I0_3") (pintype "input"))
      (node (ref "E07") (pin "2") (pinfunction "O_2") (pintype "output"))
    )
    (net (code "89") (name "Net-(E06A-I1)") (class "Default")
      (node (ref "E06") (pin "2") (pinfunction "I1_2") (pintype "input"))
      (node (ref "E07") (pin "3") (pinfunction "O_3") (pintype "output"))
    )
    (net (code "90") (name "Net-(E06A-I2)") (class "Default")
      (node (ref "E06") (pin "15") (pinfunction "I2_15") (pintype "input"))
      (node (ref "E07") (pin "13") (pinfunction "O_13") (pintype "output"))
    )
    (net (code "91") (name "Net-(E06A-L)") (class "Default")
      (node (ref "E06") (pin "1") (pinfunction "R_1") (pintype "input"))
      (node (ref "E06") (pin "10") (pinfunction "L_10") (pintype "input"))
      (node (ref "E11") (pin "1") (pinfunction "R_1") (pintype "input"))
      (node (ref "E11") (pin "10") (pinfunction "L_10") (pintype "input"))
      (node (ref "E16") (pin "1") (pinfunction "R_1") (pintype "input"))
      (node (ref "E16") (pin "10") (pinfunction "L_10") (pintype "input"))
      (node (ref "R3") (pin "1") (pinfunction "1_1") (pintype "passive"))
    )
    (net (code "92") (name "Net-(E08A-B)") (class "Default")
      (node (ref "E08") (pin "2") (pinfunction "B_2") (pintype "input"))
      (node (ref "E08") (pin "5") (pinfunction "Q_5") (pintype "output"))
    )
    (net (code "93") (name "Net-(E08A-C)") (class "Default")
      (node (ref "C38") (pin "2") (pinfunction "2_2") (pintype "passive"))
      (node (ref "E08") (pin "14") (pinfunction "C_14") (pintype "input"))
    )
    (net (code "94") (name "Net-(E08A-CLR)") (class "Default")
      (node (ref "E08") (pin "11") (pinfunction "CLR_11") (pintype "input"))
      (node (ref "E08") (pin "3") (pinfunction "CLR_3") (pintype "input"))
      (node (ref "E09") (pin "10") (pinfunction "PRE_10") (pintype "input"))
      (node (ref "E09") (pin "13") (pinfunction "CLR_13") (pintype "input"))
      (node (ref "E09") (pin "4") (pinfunction "PRE_4") (pintype "input"))
      (node (ref "E14") (pin "1") (pinfunction "CLR_1") (pintype "input"))
      (node (ref "E14") (pin "10") (pinfunction "PRE_10") (pintype "input"))
      (node (ref "E14") (pin "13") (pinfunction "CLR_13") (pintype "input"))
      (node (ref "E14") (pin "4") (pinfunction "PRE_4") (pintype "input"))
      (node (ref "R22") (pin "2") (pinfunction "2_2") (pintype "passive"))
    )
    (net (code "95") (name "Net-(E08A-R{slash}C)") (class "Default")
      (node (ref "C38") (pin "1") (pinfunction "1_1") (pintype "passive"))
      (node (ref "E08") (pin "15") (pinfunction "R/C_15") (pintype "input"))
      (node (ref "R24") (pin "1") (pinfunction "1_1") (pintype "passive"))
    )
    (net (code "96") (name "Net-(E08B-C)") (class "Default")
      (node (ref "C37") (pin "2") (pinfunction "2_2") (pintype "passive"))
      (node (ref "E08") (pin "6") (pinfunction "C_6") (pintype "input"))
    )
    (net (code "97") (name "Net-(E08B-R{slash}C)") (class "Default")
      (node (ref "C37") (pin "1") (pinfunction "1_1") (pintype "passive"))
      (node (ref "E08") (pin "7") (pinfunction "R/C_7") (pintype "input"))
      (node (ref "R23") (pin "1") (pinfunction "1_1") (pintype "passive"))
    )
    (net (code "98") (name "Net-(E08B-~{Q})") (class "Default")
      (node (ref "E08") (pin "12") (pinfunction "~{Q}_12") (pintype "output"))
      (node (ref "E09") (pin "11") (pinfunction "CLK_11") (pintype "input"))
      (node (ref "E09") (pin "3") (pinfunction "CLK_3") (pintype "input"))
      (node (ref "E19") (pin "9") (pinfunction "I0_9") (pintype "input"))
    )
    (net (code "99") (name "Net-(E09A-Q)") (class "Default")
      (node (ref "E09") (pin "5") (pinfunction "Q_5") (pintype "output"))
      (node (ref "E23") (pin "9") (pinfunction "I0_9") (pintype "input"))
      (node (ref "E27") (pin "9") (pinfunction "I0_9") (pintype "input"))
    )
    (net (code "100") (name "Net-(E09B-D)") (class "Default")
      (node (ref "E09") (pin "12") (pinfunction "D_12") (pintype "input"))
      (node (ref "E09") (pin "8") (pinfunction "~{Q}_8") (pintype "output"))
      (node (ref "E23") (pin "11") (pinfunction "I2_11") (pintype "input"))
    )
    (net (code "101") (name "Net-(E10A-B3)") (class "Default")
      (node (ref "E10") (pin "14") (pinfunction "B3_14") (pintype "input"))
      (node (ref "E37") (pin "4") (pinfunction "O_4") (pintype "output"))
    )
    (net (code "102") (name "Net-(E11A-I0)") (class "Default")
      (node (ref "E11") (pin "3") (pinfunction "I0_3") (pintype "input"))
      (node (ref "E12") (pin "2") (pinfunction "O_2") (pintype "output"))
    )
    (net (code "103") (name "Net-(E11A-I1)") (class "Default")
      (node (ref "E11") (pin "2") (pinfunction "I1_2") (pintype "input"))
      (node (ref "E12") (pin "3") (pinfunction "O_3") (pintype "output"))
    )
    (net (code "104") (name "Net-(E11A-I2)") (class "Default")
      (node (ref "E11") (pin "15") (pinfunction "I2_15") (pintype "input"))
      (node (ref "E12") (pin "13") (pinfunction "O_13") (pintype "output"))
    )
    (net (code "105") (name "Net-(E13A-C12)") (class "Default")
      (node (ref "E13") (pin "13") (pinfunction "C12_13") (pintype "input"))
      (node (ref "E13") (pin "4") (pinfunction "C34_4") (pintype "input"))
      (node (ref "E31") (pin "12") (pinfunction "O_12") (pintype "output"))
    )
    (net (code "106") (name "Net-(E13A-~{Q1})") (class "Default")
      (node (ref "E13") (pin "1") (pinfunction "~{Q1}_1") (pintype "output"))
      (node (ref "E18") (pin "13") (pinfunction "I1_13") (pintype "input"))
    )
    (net (code "107") (name "Net-(E13A-~{Q3})") (class "Default")
      (node (ref "E13") (pin "11") (pinfunction "~{Q3}_11") (pintype "output"))
      (node (ref "E18") (pin "6") (pinfunction "I1_6") (pintype "input"))
    )
    (net (code "108") (name "Net-(E13A-~{Q4})") (class "Default")
      (node (ref "E13") (pin "8") (pinfunction "~{Q4}_8") (pintype "output"))
      (node (ref "E18") (pin "8") (pinfunction "I0_8") (pintype "input"))
    )
    (net (code "109") (name "Net-(E14A-D)") (class "Default")
      (node (ref "E14") (pin "2") (pinfunction "D_2") (pintype "input"))
      (node (ref "E14") (pin "8") (pinfunction "~{Q}_8") (pintype "output"))
      (node (ref "E23") (pin "3") (pinfunction "I0_3") (pintype "input"))
      (node (ref "E39") (pin "5") (pinfunction "I_5") (pintype "input"))
    )
    (net (code "110") (name "Net-(E16A-I0)") (class "Default")
      (node (ref "E16") (pin "3") (pinfunction "I0_3") (pintype "input"))
      (node (ref "E17") (pin "2") (pinfunction "O_2") (pintype "output"))
    )
    (net (code "111") (name "Net-(E16A-I1)") (class "Default")
      (node (ref "E16") (pin "2") (pinfunction "I1_2") (pintype "input"))
      (node (ref "E17") (pin "3") (pinfunction "O_3") (pintype "output"))
    )
    (net (code "112") (name "Net-(E18B-O)") (class "Default")
      (node (ref "E18") (pin "4") (pinfunction "O_4") (pintype "open_collector"))
      (node (ref "E39") (pin "13") (pinfunction "I_13") (pintype "input"))
      (node (ref "R10") (pin "1") (pinfunction "1_1") (pintype "passive"))
    )
    (net (code "113") (name "Net-(E18C-O)") (class "Default")
      (node (ref "E18") (pin "10") (pinfunction "O_10") (pintype "open_collector"))
      (node (ref "E39") (pin "3") (pinfunction "I_3") (pintype "input"))
      (node (ref "R9") (pin "1") (pinfunction "1_1") (pintype "passive"))
    )
    (net (code "114") (name "Net-(E18D-O)") (class "Default")
      (node (ref "E18") (pin "11") (pinfunction "O_11") (pintype "open_collector"))
      (node (ref "E39") (pin "1") (pinfunction "I_1") (pintype "input"))
      (node (ref "R8") (pin "1") (pinfunction "1_1") (pintype "passive"))
    )
    (net (code "115") (name "Net-(E19A-I0)") (class "Default")
      (node (ref "E19") (pin "1") (pinfunction "I0_1") (pintype "input"))
      (node (ref "E23") (pin "8") (pinfunction "O_8") (pintype "output"))
    )
    (net (code "116") (name "Net-(E19A-I1)") (class "Default")
      (node (ref "E19") (pin "2") (pinfunction "I1_2") (pintype "input"))
      (node (ref "E23") (pin "12") (pinfunction "O_12") (pintype "output"))
    )
    (net (code "117") (name "Net-(E19B-I0)") (class "Default")
      (node (ref "E19") (pin "4") (pinfunction "I0_4") (pintype "input"))
      (node (ref "E27") (pin "8") (pinfunction "O_8") (pintype "output"))
    )
    (net (code "118") (name "Net-(E19B-I1)") (class "Default")
      (node (ref "E19") (pin "5") (pinfunction "I1_5") (pintype "input"))
      (node (ref "E23") (pin "6") (pinfunction "O_6") (pintype "output"))
    )
    (net (code "119") (name "Net-(E19C-I1)") (class "Default")
      (node (ref "E19") (pin "10") (pinfunction "I1_10") (pintype "input"))
      (node (ref "E43") (pin "1") (pinfunction "O_1") (pintype "open_collector"))
      (node (ref "E43") (pin "4") (pinfunction "O_4") (pintype "open_collector"))
      (node (ref "R21") (pin "1") (pinfunction "1_1") (pintype "passive"))
    )
    (net (code "120") (name "Net-(E19D-I0)") (class "Default")
      (node (ref "E19") (pin "12") (pinfunction "I0_12") (pintype "input"))
      (node (ref "E26") (pin "1") (pinfunction "I_1") (pintype "input"))
      (node (ref "E40") (pin "8") (pinfunction "O_8") (pintype "output"))
    )
    (net (code "121") (name "Net-(E19D-O)") (class "Default")
      (node (ref "E19") (pin "11") (pinfunction "O_11") (pintype "output"))
      (node (ref "E30") (pin "13") (pinfunction "CLR_13") (pintype "input"))
    )
    (net (code "122") (name "Net-(E20A-I0)") (class "Default")
      (node (ref "E20") (pin "4") (pinfunction "I0_4") (pintype "input"))
      (node (ref "E20") (pin "7") (pinfunction "I1_7") (pintype "input"))
      (node (ref "E24") (pin "10") (pinfunction "I4_10") (pintype "input"))
      (node (ref "E28") (pin "14") (pinfunction "O_14") (pintype "output"))
    )
    (net (code "123") (name "Net-(E20A-O)") (class "Default")
      (node (ref "E20") (pin "3") (pinfunction "O_3") (pintype "output"))
      (node (ref "W2W1") (pin "3") (pinfunction "3_3") (pintype "passive"))
    )
    (net (code "124") (name "Net-(E20B-O)") (class "Default")
      (node (ref "E20") (pin "2") (pinfunction "O_2") (pintype "output"))
      (node (ref "W4W3") (pin "3") (pinfunction "3_3") (pintype "passive"))
    )
    (net (code "125") (name "Net-(E21A-C)") (class "Default")
      (node (ref "E21") (pin "6") (pinfunction "C_6") (pintype "input"))
      (node (ref "E22") (pin "6") (pinfunction "O_6") (pintype "output"))
      (node (ref "E29") (pin "6") (pinfunction "C_6") (pintype "input"))
    )
    (net (code "126") (name "Net-(E21A-I0)") (class "Default")
      (node (ref "E21") (pin "1") (pinfunction "R_1") (pintype "input"))
      (node (ref "E21") (pin "10") (pinfunction "L_10") (pintype "input"))
      (node (ref "E21") (pin "14") (pinfunction "I3_14") (pintype "input"))
      (node (ref "E21") (pin "15") (pinfunction "I2_15") (pintype "input"))
      (node (ref "E21") (pin "2") (pinfunction "I1_2") (pintype "input"))
      (node (ref "E21") (pin "3") (pinfunction "I0_3") (pintype "input"))
      (node (ref "E29") (pin "1") (pinfunction "R_1") (pintype "input"))
      (node (ref "E29") (pin "10") (pinfunction "L_10") (pintype "input"))
      (node (ref "E29") (pin "14") (pinfunction "I3_14") (pintype "input"))
      (node (ref "E29") (pin "15") (pinfunction "I2_15") (pintype "input"))
      (node (ref "E29") (pin "2") (pinfunction "I1_2") (pintype "input"))
      (node (ref "E29") (pin "3") (pinfunction "I0_3") (pintype "input"))
      (node (ref "R2") (pin "1") (pinfunction "1_1") (pintype "passive"))
    )
    (net (code "127") (name "Net-(E22A-I0)") (class "Default")
      (node (ref "E22") (pin "1") (pinfunction "I0_1") (pintype "input"))
      (node (ref "E22") (pin "11") (pinfunction "O_11") (pintype "output"))
    )
    (net (code "128") (name "Net-(E22C-I1)") (class "Default")
      (node (ref "E22") (pin "10") (pinfunction "I1_10") (pintype "input"))
      (node (ref "E31") (pin "8") (pinfunction "O_8") (pintype "output"))
    )
    (net (code "129") (name "Net-(E22C-O)") (class "Default")
      (node (ref "E22") (pin "8") (pinfunction "O_8") (pintype "output"))
      (node (ref "E26") (pin "9") (pinfunction "I_9") (pintype "input"))
    )
    (net (code "130") (name "Net-(E24A-I5)") (class "Default")
      (node (ref "E24") (pin "11") (pinfunction "I5_11") (pintype "input"))
      (node (ref "W2W1") (pin "2") (pinfunction "2_2") (pintype "passive"))
    )
    (net (code "131") (name "Net-(E24A-I6)") (class "Default")
      (node (ref "E24") (pin "12") (pinfunction "I6_12") (pintype "input"))
      (node (ref "W4W3") (pin "2") (pinfunction "2_2") (pintype "passive"))
    )
    (net (code "132") (name "Net-(E24A-O)") (class "Default")
      (node (ref "E24") (pin "3") (pinfunction "O_3") (pintype "output"))
      (node (ref "E26") (pin "11") (pinfunction "I_11") (pintype "input"))
      (node (ref "E33") (pin "5") (pinfunction "I0_5") (pintype "input"))
      (node (ref "E33") (pin "6") (pinfunction "I1_6") (pintype "input"))
    )
    (net (code "133") (name "Net-(E26B-I)") (class "Default")
      (node (ref "E26") (pin "3") (pinfunction "I_3") (pintype "input"))
      (node (ref "E43") (pin "10") (pinfunction "O_10") (pintype "open_collector"))
      (node (ref "E43") (pin "11") (pinfunction "I0_11") (pintype "input"))
      (node (ref "R14") (pin "2") (pinfunction "2_2") (pintype "passive"))
    )
    (net (code "134") (name "Net-(E26B-O)") (class "Default")
      (node (ref "E26") (pin "4") (pinfunction "O_4") (pintype "output"))
      (node (ref "E46") (pin "11") (pinfunction "I0_11") (pintype "input"))
    )
    (net (code "135") (name "Net-(E27B-O)") (class "Default")
      (node (ref "E27") (pin "6") (pinfunction "O_6") (pintype "output"))
      (node (ref "E37") (pin "2") (pinfunction "I0_2") (pintype "input"))
      (node (ref "E38") (pin "1") (pinfunction "I0_1") (pintype "input"))
    )
    (net (code "136") (name "Net-(E30A-CLR)") (class "Default")
      (node (ref "E30") (pin "1") (pinfunction "CLR_1") (pintype "input"))
      (node (ref "E37") (pin "10") (pinfunction "O_10") (pintype "output"))
    )
    (net (code "137") (name "Net-(E30A-PRE)") (class "Default")
      (node (ref "E30") (pin "10") (pinfunction "PRE_10") (pintype "input"))
      (node (ref "E30") (pin "4") (pinfunction "PRE_4") (pintype "input"))
      (node (ref "E34") (pin "10") (pinfunction "PRE_10") (pintype "input"))
      (node (ref "E34") (pin "4") (pinfunction "PRE_4") (pintype "input"))
      (node (ref "R12") (pin "1") (pinfunction "1_1") (pintype "passive"))
    )
    (net (code "138") (name "Net-(E31E-I)") (class "Default")
      (node (ref "E31") (pin "11") (pinfunction "I_11") (pintype "input"))
      (node (ref "E37") (pin "1") (pinfunction "O_1") (pintype "output"))
    )
    (net (code "139") (name "Net-(E31E-O)") (class "Default")
      (node (ref "E31") (pin "10") (pinfunction "O_10") (pintype "output"))
      (node (ref "E35") (pin "11") (pinfunction "I2_11") (pintype "input"))
      (node (ref "E35") (pin "13") (pinfunction "I2_13") (pintype "input"))
    )
    (net (code "140") (name "Net-(E32A-O)") (class "Default")
      (node (ref "E32") (pin "2") (pinfunction "O_2") (pintype "output"))
      (node (ref "E41") (pin "11") (pinfunction "I0_11") (pintype "input"))
    )
    (net (code "141") (name "Net-(E32B-O)") (class "Default")
      (node (ref "E32") (pin "4") (pinfunction "O_4") (pintype "output"))
      (node (ref "E41") (pin "9") (pinfunction "I1_9") (pintype "input"))
    )
    (net (code "142") (name "Net-(E32C-O)") (class "Default")
      (node (ref "E32") (pin "6") (pinfunction "O_6") (pintype "output"))
      (node (ref "E41") (pin "3") (pinfunction "I1_3") (pintype "input"))
    )
    (net (code "143") (name "Net-(E32D-I)") (class "Default")
      (node (ref "E32") (pin "9") (pinfunction "I_9") (pintype "input"))
      (node (ref "Q1") (pin "3") (pinfunction "C_3") (pintype "passive"))
      (node (ref "R27") (pin "1") (pinfunction "1_1") (pintype "passive"))
    )
    (net (code "144") (name "Net-(E33A-I0)") (class "Default")
      (node (ref "E33") (pin "11") (pinfunction "I0_11") (pintype "input"))
      (node (ref "E33") (pin "2") (pinfunction "I0_2") (pintype "input"))
      (node (ref "E44") (pin "2") (pinfunction "O_2") (pintype "output"))
      (node (ref "E45") (pin "1") (pinfunction "C_1") (pintype "input"))
    )
    (net (code "145") (name "Net-(E33A-I1)") (class "Default")
      (node (ref "E33") (pin "3") (pinfunction "I1_3") (pintype "input"))
      (node (ref "E44") (pin "14") (pinfunction "O_14") (pintype "output"))
      (node (ref "E45") (pin "14") (pinfunction "B_14") (pintype "input"))
    )
    (net (code "146") (name "Net-(E35A-O)") (class "Default")
      (node (ref "E35") (pin "12") (pinfunction "O_12") (pintype "output"))
      (node (ref "E35") (pin "3") (pinfunction "I0_3") (pintype "input"))
    )
    (net (code "147") (name "Net-(E35B-I1)") (class "Default")
      (node (ref "E35") (pin "4") (pinfunction "I1_4") (pintype "input"))
      (node (ref "E35") (pin "8") (pinfunction "O_8") (pintype "output"))
    )
    (net (code "148") (name "Net-(E36A-QA)") (class "Default")
      (node (ref "E36") (pin "12") (pinfunction "QA_12") (pintype "output"))
      (node (ref "E41") (pin "8") (pinfunction "I0_8") (pintype "input"))
    )
    (net (code "149") (name "Net-(E36A-R0(1))") (class "Default")
      (node (ref "E36") (pin "2") (pinfunction "R0(1)_2") (pintype "input"))
      (node (ref "E36") (pin "3") (pinfunction "R0(2)_3") (pintype "input"))
      (node (ref "E38") (pin "6") (pinfunction "O_6") (pintype "output"))
    )
    (net (code "150") (name "Net-(E38A-O)") (class "Default")
      (node (ref "E38") (pin "3") (pinfunction "O_3") (pintype "output"))
      (node (ref "E38") (pin "4") (pinfunction "I0_4") (pintype "input"))
    )
    (net (code "151") (name "Net-(E38C-I1)") (class "Default")
      (node (ref "E38") (pin "10") (pinfunction "I1_10") (pintype "input"))
      (node (ref "E38") (pin "11") (pinfunction "O_11") (pintype "output"))
    )
    (net (code "152") (name "Net-(E42A-O)") (class "Default")
      (node (ref "E42") (pin "3") (pinfunction "O_3") (pintype "open_collector"))
      (node (ref "E43") (pin "5") (pinfunction "I0_5") (pintype "input"))
      (node (ref "R20") (pin "1") (pinfunction "1_1") (pintype "passive"))
    )
    (net (code "153") (name "Net-(E42B-O)") (class "Default")
      (node (ref "E42") (pin "4") (pinfunction "O_4") (pintype "open_collector"))
      (node (ref "E43") (pin "3") (pinfunction "I1_3") (pintype "input"))
      (node (ref "R19") (pin "1") (pinfunction "1_1") (pintype "passive"))
    )
    (net (code "154") (name "Net-(E43C-I1)") (class "Default")
      (node (ref "E43") (pin "13") (pinfunction "O_13") (pintype "open_collector"))
      (node (ref "E43") (pin "9") (pinfunction "I1_9") (pintype "input"))
      (node (ref "R13") (pin "2") (pinfunction "2_2") (pintype "passive"))
    )
    (net (code "155") (name "Net-(E44D-O)") (class "Default")
      (node (ref "E44") (pin "13") (pinfunction "O_13") (pintype "output"))
      (node (ref "E45") (pin "15") (pinfunction "A_15") (pintype "input"))
    )
    (net (code "156") (name "Net-(Q1-B)") (class "Default")
      (node (ref "D1") (pin "C") (pinfunction "C_C") (pintype "passive"))
      (node (ref "Q1") (pin "2") (pinfunction "B_2") (pintype "passive"))
      (node (ref "R48") (pin "2") (pinfunction "2_2") (pintype "passive"))
    )
    (net (code "157") (name "Net-(Q1-E)") (class "Default")
      (node (ref "D5") (pin "C") (pinfunction "C_C") (pintype "passive"))
      (node (ref "Q1") (pin "1") (pinfunction "E_1") (pintype "passive"))
      (node (ref "R41") (pin "2") (pinfunction "2_2") (pintype "passive"))
    )
    (net (code "158") (name "Net-(Q2-E)") (class "Default")
      (node (ref "D8") (pin "A") (pinfunction "A_A") (pintype "passive"))
      (node (ref "Q2") (pin "1") (pinfunction "E_1") (pintype "passive"))
    )
    (net (code "159") (name "Net-(Q3-E)") (class "Default")
      (node (ref "D9") (pin "A") (pinfunction "A_A") (pintype "passive"))
      (node (ref "Q3") (pin "1") (pinfunction "E_1") (pintype "passive"))
    )
    (net (code "160") (name "Net-(Q4-E)") (class "Default")
      (node (ref "D7") (pin "A") (pinfunction "A_A") (pintype "passive"))
      (node (ref "Q4") (pin "1") (pinfunction "E_1") (pintype "passive"))
    )
    (net (code "161") (name "Net-(Q5-E)") (class "Default")
      (node (ref "D10") (pin "A") (pinfunction "A_A") (pintype "passive"))
      (node (ref "Q5") (pin "1") (pinfunction "E_1") (pintype "passive"))
    )
    (net (code "162") (name "Net-(R26-A)") (class "Default")
      (node (ref "R26") (pin "1") (pinfunction "A_1") (pintype "passive"))
      (node (ref "R43") (pin "2") (pinfunction "2_2") (pintype "passive"))
    )
    (net (code "163") (name "RD00") (class "Default")
      (node (ref "E16") (pin "4") (pinfunction "D_4") (pintype "input"))
      (node (ref "J1") (pin "D") (pinfunction "4_D") (pintype "bidirectional"))
      (node (ref "R4") (pin "1") (pinfunction "1_1") (pintype "passive"))
    )
    (net (code "164") (name "RD01") (class "Default")
      (node (ref "E11") (pin "4") (pinfunction "D_4") (pintype "input"))
      (node (ref "J1") (pin "L") (pinfunction "10_L") (pintype "bidirectional"))
      (node (ref "R5") (pin "1") (pinfunction "1_1") (pintype "passive"))
    )
    (net (code "165") (name "RD02") (class "Default")
      (node (ref "E06") (pin "4") (pinfunction "D_4") (pintype "input"))
      (node (ref "J1") (pin "V") (pinfunction "18_V") (pintype "bidirectional"))
      (node (ref "R7") (pin "1") (pinfunction "1_1") (pintype "passive"))
    )
    (net (code "166") (name "RMT") (class "Default")
      (node (ref "E21") (pin "4") (pinfunction "D_4") (pintype "input"))
      (node (ref "J1") (pin "F") (pinfunction "6_F") (pintype "bidirectional"))
      (node (ref "R1") (pin "1") (pinfunction "1_1") (pintype "passive"))
    )
    (net (code "167") (name "RUN") (class "Default")
      (node (ref "E20") (pin "9") (pinfunction "I0_9") (pintype "input"))
      (node (ref "EDGE$") (pin "BU2") (pinfunction "1_BU2") (pintype "bidirectional"))
    )
    (net (code "168") (name "SEL_ECHO") (class "Default")
      (node (ref "J1") (pin "N") (pinfunction "12_N") (pintype "bidirectional"))
      (node (ref "Q2") (pin "2") (pinfunction "B_2") (pintype "passive"))
      (node (ref "Q5") (pin "2") (pinfunction "B_2") (pintype "passive"))
      (node (ref "R30") (pin "2") (pinfunction "2_2") (pintype "passive"))
      (node (ref "R31") (pin "2") (pinfunction "2_2") (pintype "passive"))
      (node (ref "R32") (pin "2") (pinfunction "2_2") (pintype "passive"))
      (node (ref "R33") (pin "2") (pinfunction "2_2") (pintype "passive"))
      (node (ref "R34") (pin "2") (pinfunction "2_2") (pintype "passive"))
    )
    (net (code "169") (name "SR00") (class "Default")
      (node (ref "E05") (pin "10") (pinfunction "A2_10") (pintype "input"))
      (node (ref "E13") (pin "6") (pinfunction "D3_6") (pintype "input"))
      (node (ref "E16") (pin "11") (pinfunction "Q3_11") (pintype "output"))
    )
    (net (code "170") (name "SR01") (class "Default")
      (node (ref "E05") (pin "15") (pinfunction "A3_15") (pintype "input"))
      (node (ref "E11") (pin "11") (pinfunction "Q3_11") (pintype "output"))
      (node (ref "E13") (pin "7") (pinfunction "D4_7") (pintype "input"))
    )
    (net (code "171") (name "SR02") (class "Default")
      (node (ref "E05") (pin "6") (pinfunction "A1_6") (pintype "input"))
      (node (ref "E06") (pin "11") (pinfunction "Q3_11") (pintype "output"))
      (node (ref "E13") (pin "2") (pinfunction "D1_2") (pintype "input"))
    )
    (net (code "172") (name "SR03") (class "Default")
      (node (ref "E05") (pin "1") (pinfunction "A0_1") (pintype "input"))
      (node (ref "E16") (pin "9") (pinfunction "Q2_9") (pintype "output"))
    )
    (net (code "173") (name "SR04") (class "Default")
      (node (ref "E10") (pin "10") (pinfunction "A2_10") (pintype "input"))
      (node (ref "E11") (pin "9") (pinfunction "Q2_9") (pintype "output"))
    )
    (net (code "174") (name "SR05") (class "Default")
      (node (ref "E06") (pin "9") (pinfunction "Q2_9") (pintype "output"))
      (node (ref "E10") (pin "15") (pinfunction "A3_15") (pintype "input"))
    )
    (net (code "175") (name "SR06") (class "Default")
      (node (ref "E10") (pin "6") (pinfunction "A1_6") (pintype "input"))
      (node (ref "E16") (pin "7") (pinfunction "Q1_7") (pintype "output"))
    )
    (net (code "176") (name "SR07") (class "Default")
      (node (ref "E10") (pin "1") (pinfunction "A0_1") (pintype "input"))
      (node (ref "E11") (pin "7") (pinfunction "Q1_7") (pintype "output"))
    )
    (net (code "177") (name "SR08") (class "Default")
      (node (ref "E06") (pin "7") (pinfunction "Q1_7") (pintype "output"))
      (node (ref "E15") (pin "10") (pinfunction "A2_10") (pintype "input"))
    )
    (net (code "178") (name "SR09") (class "Default")
      (node (ref "E15") (pin "15") (pinfunction "A3_15") (pintype "input"))
      (node (ref "E16") (pin "5") (pinfunction "Q0_5") (pintype "output"))
    )
    (net (code "179") (name "SR10") (class "Default")
      (node (ref "E11") (pin "5") (pinfunction "Q0_5") (pintype "output"))
      (node (ref "E15") (pin "6") (pinfunction "A1_6") (pintype "input"))
    )
    (net (code "180") (name "SR11") (class "Default")
      (node (ref "E06") (pin "5") (pinfunction "Q0_5") (pintype "output"))
      (node (ref "E15") (pin "1") (pinfunction "A0_1") (pintype "input"))
    )
    (net (code "181") (name "SYNC") (class "Default")
      (node (ref "E09") (pin "9") (pinfunction "Q_9") (pintype "output"))
      (node (ref "E27") (pin "11") (pinfunction "I2_11") (pintype "input"))
      (node (ref "E42") (pin "2") (pinfunction "I1_2") (pintype "input"))
      (node (ref "E42") (pin "5") (pinfunction "I0_5") (pintype "input"))
    )
    (net (code "182") (name "S{slash}~{G}") (class "Default")
      (node (ref "E46") (pin "13") (pinfunction "O_13") (pintype "open_collector"))
      (node (ref "J1") (pin "JJ") (pinfunction "30_JJ") (pintype "bidirectional"))
    )
    (net (code "183") (name "TP3") (class "Default")
      (node (ref "E20") (pin "11") (pinfunction "I0_11") (pintype "input"))
      (node (ref "EDGE$") (pin "CH2") (pinfunction "1_CH2") (pintype "bidirectional"))
    )
    (net (code "184") (name "TP4") (class "Default")
      (node (ref "E44") (pin "5") (pinfunction "I1_5") (pintype "input"))
      (node (ref "EDGE$") (pin "CJ2") (pinfunction "1_CJ2") (pintype "bidirectional"))
    )
    (net (code "185") (name "TPG0") (class "Default")
      (node (ref "E14") (pin "9") (pinfunction "Q_9") (pintype "output"))
      (node (ref "E23") (pin "13") (pinfunction "I2_13") (pintype "input"))
    )
    (net (code "186") (name "T{slash}M_ENABLE") (class "Default")
      (node (ref "E46") (pin "4") (pinfunction "O_4") (pintype "open_collector"))
      (node (ref "J1") (pin "NN") (pinfunction "34_NN") (pintype "bidirectional"))
    )
    (net (code "187") (name "UNITH") (class "Default")
      (node (ref "E39") (pin "10") (pinfunction "O_10") (pintype "open_collector"))
      (node (ref "J1") (pin "LL") (pinfunction "32_LL") (pintype "bidirectional"))
    )
    (net (code "188") (name "VCC") (class "Default")
      (node (ref "C1") (pin "1") (pinfunction "1_1") (pintype "passive"))
      (node (ref "C10") (pin "1") (pinfunction "1_1") (pintype "passive"))
      (node (ref "C11") (pin "1") (pinfunction "1_1") (pintype "passive"))
      (node (ref "C12") (pin "1") (pinfunction "1_1") (pintype "passive"))
      (node (ref "C13") (pin "1") (pinfunction "1_1") (pintype "passive"))
      (node (ref "C14") (pin "1") (pinfunction "1_1") (pintype "passive"))
      (node (ref "C15") (pin "1") (pinfunction "1_1") (pintype "passive"))
      (node (ref "C16") (pin "1") (pinfunction "1_1") (pintype "passive"))
      (node (ref "C17") (pin "1") (pinfunction "1_1") (pintype "passive"))
      (node (ref "C18") (pin "1") (pinfunction "1_1") (pintype "passive"))
      (node (ref "C19") (pin "1") (pinfunction "1_1") (pintype "passive"))
      (node (ref "C2") (pin "1") (pinfunction "1_1") (pintype "passive"))
      (node (ref "C20") (pin "1") (pinfunction "1_1") (pintype "passive"))
      (node (ref "C21") (pin "1") (pinfunction "1_1") (pintype "passive"))
      (node (ref "C22") (pin "1") (pinfunction "1_1") (pintype "passive"))
      (node (ref "C23") (pin "1") (pinfunction "1_1") (pintype "passive"))
      (node (ref "C24") (pin "1") (pinfunction "1_1") (pintype "passive"))
      (node (ref "C25") (pin "1") (pinfunction "1_1") (pintype "passive"))
      (node (ref "C26") (pin "1") (pinfunction "1_1") (pintype "passive"))
      (node (ref "C27") (pin "1") (pinfunction "1_1") (pintype "passive"))
      (node (ref "C28") (pin "1") (pinfunction "1_1") (pintype "passive"))
      (node (ref "C29") (pin "1") (pinfunction "1_1") (pintype "passive"))
      (node (ref "C3") (pin "1") (pinfunction "1_1") (pintype "passive"))
      (node (ref "C30") (pin "1") (pinfunction "1_1") (pintype "passive"))
      (node (ref "C31") (pin "1") (pinfunction "1_1") (pintype "passive"))
      (node (ref "C32") (pin "1") (pinfunction "1_1") (pintype "passive"))
      (node (ref "C33") (pin "1") (pinfunction "1_1") (pintype "passive"))
      (node (ref "C34") (pin "+") (pinfunction "+_+") (pintype "passive"))
      (node (ref "C35") (pin "+") (pinfunction "+_+") (pintype "passive"))
      (node (ref "C4") (pin "1") (pinfunction "1_1") (pintype "passive"))
      (node (ref "C43") (pin "1") (pinfunction "1_1") (pintype "passive"))
      (node (ref "C45") (pin "1") (pinfunction "1_1") (pintype "passive"))
      (node (ref "C46") (pin "+") (pinfunction "+_+") (pintype "passive"))
      (node (ref "C5") (pin "1") (pinfunction "1_1") (pintype "passive"))
      (node (ref "C6") (pin "1") (pinfunction "1_1") (pintype "passive"))
      (node (ref "C7") (pin "1") (pinfunction "1_1") (pintype "passive"))
      (node (ref "C8") (pin "1") (pinfunction "1_1") (pintype "passive"))
      (node (ref "C9") (pin "1") (pinfunction "1_1") (pintype "passive"))
      (node (ref "E25") (pin "14") (pinfunction "14_14") (pintype "passive"))
      (node (ref "EDGE$") (pin "AA2") (pinfunction "1_AA2") (pintype "bidirectional"))
      (node (ref "EDGE$") (pin "BA2") (pinfunction "1_BA2") (pintype "bidirectional"))
      (node (ref "EDGE$") (pin "CA2") (pinfunction "1_CA2") (pintype "bidirectional"))
      (node (ref "R1") (pin "2") (pinfunction "2_2") (pintype "passive"))
      (node (ref "R10") (pin "2") (pinfunction "2_2") (pintype "passive"))
      (node (ref "R11") (pin "2") (pinfunction "2_2") (pintype "passive"))
      (node (ref "R12") (pin "2") (pinfunction "2_2") (pintype "passive"))
      (node (ref "R13") (pin "1") (pinfunction "1_1") (pintype "passive"))
      (node (ref "R14") (pin "1") (pinfunction "1_1") (pintype "passive"))
      (node (ref "R15") (pin "2") (pinfunction "2_2") (pintype "passive"))
      (node (ref "R16") (pin "2") (pinfunction "2_2") (pintype "passive"))
      (node (ref "R17") (pin "2") (pinfunction "2_2") (pintype "passive"))
      (node (ref "R18") (pin "2") (pinfunction "2_2") (pintype "passive"))
      (node (ref "R19") (pin "2") (pinfunction "2_2") (pintype "passive"))
      (node (ref "R2") (pin "2") (pinfunction "2_2") (pintype "passive"))
      (node (ref "R20") (pin "2") (pinfunction "2_2") (pintype "passive"))
      (node (ref "R21") (pin "2") (pinfunction "2_2") (pintype "passive"))
      (node (ref "R22") (pin "1") (pinfunction "1_1") (pintype "passive"))
      (node (ref "R23") (pin "2") (pinfunction "2_2") (pintype "passive"))
      (node (ref "R24") (pin "2") (pinfunction "2_2") (pintype "passive"))
      (node (ref "R26") (pin "2") (pinfunction "S_2") (pintype "passive"))
      (node (ref "R26") (pin "3") (pinfunction "E_3") (pintype "passive"))
      (node (ref "R27") (pin "2") (pinfunction "2_2") (pintype "passive"))
      (node (ref "R3") (pin "2") (pinfunction "2_2") (pintype "passive"))
      (node (ref "R4") (pin "2") (pinfunction "2_2") (pintype "passive"))
      (node (ref "R42") (pin "1") (pinfunction "1_1") (pintype "passive"))
      (node (ref "R5") (pin "2") (pinfunction "2_2") (pintype "passive"))
      (node (ref "R6") (pin "2") (pinfunction "2_2") (pintype "passive"))
      (node (ref "R7") (pin "2") (pinfunction "2_2") (pintype "passive"))
      (node (ref "R8") (pin "2") (pinfunction "2_2") (pintype "passive"))
      (node (ref "R9") (pin "2") (pinfunction "2_2") (pintype "passive"))
    )
    (net (code "189") (name "WD_ENAB") (class "Default")
      (node (ref "E46") (pin "10") (pinfunction "O_10") (pintype "open_collector"))
      (node (ref "J1") (pin "Z") (pinfunction "22_Z") (pintype "bidirectional"))
    )
    (net (code "190") (name "WPT") (class "Default")
      (node (ref "E39") (pin "6") (pinfunction "O_6") (pintype "open_collector"))
      (node (ref "J1") (pin "BB") (pinfunction "24_BB") (pintype "bidirectional"))
    )
    (net (code "191") (name "WRT_ECHO") (class "Default")
      (node (ref "C47") (pin "1") (pinfunction "1_1") (pintype "passive"))
      (node (ref "J1") (pin "T") (pinfunction "16_T") (pintype "bidirectional"))
      (node (ref "R48") (pin "1") (pinfunction "1_1") (pintype "passive"))
    )
    (net (code "192") (name "unconnected-(E04A-Q-Pad13)") (class "Default")
      (node (ref "E04") (pin "13") (pinfunction "Q_13") (pintype "output"))
    )
    (net (code "193") (name "unconnected-(E04B-~{Q}-Pad12)") (class "Default")
      (node (ref "E04") (pin "12") (pinfunction "~{Q}_12") (pintype "output"))
    )
    (net (code "194") (name "unconnected-(E06A-Q4-Pad12)") (class "Default")
      (node (ref "E06") (pin "12") (pinfunction "Q4_12") (pintype "output"))
    )
    (net (code "195") (name "unconnected-(E08A-~{Q}-Pad4)") (class "Default")
      (node (ref "E08") (pin "4") (pinfunction "~{Q}_4") (pintype "output"))
    )
    (net (code "196") (name "unconnected-(E09A-~{Q}-Pad6)") (class "Default")
      (node (ref "E09") (pin "6") (pinfunction "~{Q}_6") (pintype "output"))
    )
    (net (code "197") (name "unconnected-(E11A-Q4-Pad12)") (class "Default")
      (node (ref "E11") (pin "12") (pinfunction "Q4_12") (pintype "output"))
    )
    (net (code "198") (name "unconnected-(E13A-D2-Pad3)") (class "Default")
      (node (ref "E13") (pin "3") (pinfunction "D2_3") (pintype "input"))
    )
    (net (code "199") (name "unconnected-(E13A-Q1-Pad16)") (class "Default")
      (node (ref "E13") (pin "16") (pinfunction "Q1_16") (pintype "output"))
    )
    (net (code "200") (name "unconnected-(E13A-Q2-Pad15)") (class "Default")
      (node (ref "E13") (pin "15") (pinfunction "Q2_15") (pintype "output"))
    )
    (net (code "201") (name "unconnected-(E13A-Q3-Pad10)") (class "Default")
      (node (ref "E13") (pin "10") (pinfunction "Q3_10") (pintype "output"))
    )
    (net (code "202") (name "unconnected-(E13A-Q4-Pad9)") (class "Default")
      (node (ref "E13") (pin "9") (pinfunction "Q4_9") (pintype "output"))
    )
    (net (code "203") (name "unconnected-(E13A-~{Q2}-Pad14)") (class "Default")
      (node (ref "E13") (pin "14") (pinfunction "~{Q2}_14") (pintype "output"))
    )
    (net (code "204") (name "unconnected-(E16A-Q4-Pad12)") (class "Default")
      (node (ref "E16") (pin "12") (pinfunction "Q4_12") (pintype "output"))
    )
    (net (code "205") (name "unconnected-(E21A-Q4-Pad12)") (class "Default")
      (node (ref "E21") (pin "12") (pinfunction "Q4_12") (pintype "output"))
    )
    (net (code "206") (name "unconnected-(E25-Pad1)") (class "Default")
      (node (ref "E25") (pin "1") (pinfunction "1_1") (pintype "passive"))
    )
    (net (code "207") (name "unconnected-(E25-Pad2)") (class "Default")
      (node (ref "E25") (pin "2") (pinfunction "2_2") (pintype "passive"))
    )
    (net (code "208") (name "unconnected-(E25-Pad3)") (class "Default")
      (node (ref "E25") (pin "3") (pinfunction "3_3") (pintype "passive"))
    )
    (net (code "209") (name "unconnected-(E25-Pad4)") (class "Default")
      (node (ref "E25") (pin "4") (pinfunction "4_4") (pintype "passive"))
    )
    (net (code "210") (name "unconnected-(E25-Pad5)") (class "Default")
      (node (ref "E25") (pin "5") (pinfunction "5_5") (pintype "passive"))
    )
    (net (code "211") (name "unconnected-(E25-Pad6)") (class "Default")
      (node (ref "E25") (pin "6") (pinfunction "6_6") (pintype "passive"))
    )
    (net (code "212") (name "unconnected-(E25-Pad8)") (class "Default")
      (node (ref "E25") (pin "8") (pinfunction "8_8") (pintype "passive"))
    )
    (net (code "213") (name "unconnected-(E25-Pad9)") (class "Default")
      (node (ref "E25") (pin "9") (pinfunction "9_9") (pintype "passive"))
    )
    (net (code "214") (name "unconnected-(E25-Pad10)") (class "Default")
      (node (ref "E25") (pin "10") (pinfunction "10_10") (pintype "passive"))
    )
    (net (code "215") (name "unconnected-(E25-Pad11)") (class "Default")
      (node (ref "E25") (pin "11") (pinfunction "11_11") (pintype "passive"))
    )
    (net (code "216") (name "unconnected-(E25-Pad12)") (class "Default")
      (node (ref "E25") (pin "12") (pinfunction "12_12") (pintype "passive"))
    )
    (net (code "217") (name "unconnected-(E25-Pad13)") (class "Default")
      (node (ref "E25") (pin "13") (pinfunction "13_13") (pintype "passive"))
    )
    (net (code "218") (name "unconnected-(E29A-Q2-Pad9)") (class "Default")
      (node (ref "E29") (pin "9") (pinfunction "Q2_9") (pintype "output"))
    )
    (net (code "219") (name "unconnected-(E29A-Q3-Pad11)") (class "Default")
      (node (ref "E29") (pin "11") (pinfunction "Q3_11") (pintype "output"))
    )
    (net (code "220") (name "unconnected-(E29A-Q4-Pad12)") (class "Default")
      (node (ref "E29") (pin "12") (pinfunction "Q4_12") (pintype "output"))
    )
    (net (code "221") (name "unconnected-(E36A-QB-Pad9)") (class "Default")
      (node (ref "E36") (pin "9") (pinfunction "QB_9") (pintype "output"))
    )
    (net (code "222") (name "unconnected-(E36A-QC-Pad8)") (class "Default")
      (node (ref "E36") (pin "8") (pinfunction "QC_8") (pintype "output"))
    )
    (net (code "223") (name "unconnected-(E40A-I3-Pad4)") (class "Default")
      (node (ref "E40") (pin "4") (pinfunction "I3_4") (pintype "input"))
    )
    (net (code "224") (name "unconnected-(E40A-I5-Pad6)") (class "Default")
      (node (ref "E40") (pin "6") (pinfunction "I5_6") (pintype "input"))
    )
    (net (code "225") (name "unconnected-(E45A-0-Pad13)") (class "Default")
      (node (ref "E45") (pin "13") (pinfunction "0_13") (pintype "output"))
    )
    (net (code "226") (name "unconnected-(E45A-8-Pad6)") (class "Default")
      (node (ref "E45") (pin "6") (pinfunction "8_6") (pintype "output"))
    )
    (net (code "227") (name "unconnected-(E45A-9-Pad7)") (class "Default")
      (node (ref "E45") (pin "7") (pinfunction "9_7") (pintype "output"))
    )
    (net (code "228") (name "unconnected-(J1-14-PadR)") (class "Default")
      (node (ref "J1") (pin "R") (pinfunction "14_R") (pintype "bidirectional"))
    )
    (net (code "229") (name "~{CC_67X}") (class "Default")
      (node (ref "E07") (pin "11") (pinfunction "I0_11") (pintype "input"))
      (node (ref "E07") (pin "5") (pinfunction "I1_5") (pintype "input"))
      (node (ref "E07") (pin "6") (pinfunction "I0_6") (pintype "input"))
      (node (ref "E07") (pin "9") (pinfunction "I0_9") (pintype "input"))
      (node (ref "E12") (pin "10") (pinfunction "I1_10") (pintype "input"))
      (node (ref "E12") (pin "11") (pinfunction "I0_11") (pintype "input"))
      (node (ref "E12") (pin "4") (pinfunction "I0_4") (pintype "input"))
      (node (ref "E12") (pin "6") (pinfunction "I0_6") (pintype "input"))
      (node (ref "E17") (pin "11") (pinfunction "I0_11") (pintype "input"))
      (node (ref "E17") (pin "4") (pinfunction "I0_4") (pintype "input"))
      (node (ref "E17") (pin "6") (pinfunction "I0_6") (pintype "input"))
      (node (ref "E17") (pin "9") (pinfunction "I0_9") (pintype "input"))
      (node (ref "E26") (pin "10") (pinfunction "O_10") (pintype "output"))
      (node (ref "E44") (pin "10") (pinfunction "I1_10") (pintype "input"))
      (node (ref "E44") (pin "12") (pinfunction "I1_12") (pintype "input"))
      (node (ref "E44") (pin "6") (pinfunction "I0_6") (pintype "input"))
      (node (ref "E45") (pin "2") (pinfunction "D_2") (pintype "input"))
      (node (ref "R6") (pin "1") (pinfunction "1_1") (pintype "passive"))
    )
    (net (code "230") (name "~{CC_CLK_TE}") (class "Default")
      (node (ref "E26") (pin "6") (pinfunction "O_6") (pintype "output"))
      (node (ref "E27") (pin "2") (pinfunction "I1_2") (pintype "input"))
    )
    (net (code "231") (name "~{CC_DTP0}") (class "Default")
      (node (ref "E22") (pin "2") (pinfunction "I1_2") (pintype "input"))
      (node (ref "E31") (pin "13") (pinfunction "I_13") (pintype "input"))
      (node (ref "E31") (pin "4") (pinfunction "O_4") (pintype "output"))
      (node (ref "E38") (pin "13") (pinfunction "I1_13") (pintype "input"))
    )
    (net (code "232") (name "~{CC_DTP1}") (class "Default")
      (node (ref "E22") (pin "12") (pinfunction "I0_12") (pintype "input"))
      (node (ref "E22") (pin "5") (pinfunction "I1_5") (pintype "input"))
      (node (ref "E22") (pin "9") (pinfunction "I0_9") (pintype "input"))
      (node (ref "E31") (pin "2") (pinfunction "O_2") (pintype "output"))
    )
    (net (code "233") (name "~{CC_INIT}") (class "Default")
      (node (ref "E27") (pin "1") (pinfunction "I0_1") (pintype "input"))
      (node (ref "E32") (pin "10") (pinfunction "O_10") (pintype "output"))
      (node (ref "E34") (pin "1") (pinfunction "CLR_1") (pintype "input"))
      (node (ref "E34") (pin "13") (pinfunction "CLR_13") (pintype "input"))
      (node (ref "E40") (pin "12") (pinfunction "I7_12") (pintype "input"))
    )
    (net (code "234") (name "~{CC_RUN}") (class "Default")
      (node (ref "E20") (pin "14") (pinfunction "O_14") (pintype "output"))
      (node (ref "E26") (pin "13") (pinfunction "I_13") (pintype "input"))
      (node (ref "E40") (pin "3") (pinfunction "I2_3") (pintype "input"))
    )
    (net (code "235") (name "~{CC_SDLC}") (class "Default")
      (node (ref "E19") (pin "13") (pinfunction "I1_13") (pintype "input"))
      (node (ref "E37") (pin "12") (pinfunction "I1_12") (pintype "input"))
      (node (ref "E45") (pin "9") (pinfunction "4_9") (pintype "output"))
    )
    (net (code "236") (name "~{CC_SDLD}") (class "Default")
      (node (ref "E02") (pin "3") (pinfunction "I1_3") (pintype "input"))
      (node (ref "E06") (pin "13") (pinfunction "S_13") (pintype "input"))
      (node (ref "E11") (pin "13") (pinfunction "S_13") (pintype "input"))
      (node (ref "E16") (pin "13") (pinfunction "S_13") (pintype "input"))
      (node (ref "E27") (pin "5") (pinfunction "I2_5") (pintype "input"))
      (node (ref "E33") (pin "12") (pinfunction "I1_12") (pintype "input"))
      (node (ref "E45") (pin "3") (pinfunction "5_3") (pintype "output"))
    )
    (net (code "237") (name "~{CC_SDRC}") (class "Default")
      (node (ref "E05") (pin "9") (pinfunction "S0_9") (pintype "input"))
      (node (ref "E10") (pin "9") (pinfunction "S0_9") (pintype "input"))
      (node (ref "E15") (pin "9") (pinfunction "S0_9") (pintype "input"))
      (node (ref "E27") (pin "3") (pinfunction "I0_3") (pintype "input"))
      (node (ref "E45") (pin "4") (pinfunction "6_4") (pintype "output"))
    )
    (net (code "238") (name "~{CC_SDRD}") (class "Default")
      (node (ref "E05") (pin "7") (pinfunction "S1_7") (pintype "input"))
      (node (ref "E10") (pin "7") (pinfunction "S1_7") (pintype "input"))
      (node (ref "E15") (pin "7") (pinfunction "S1_7") (pintype "input"))
      (node (ref "E27") (pin "4") (pinfunction "I1_4") (pintype "input"))
      (node (ref "E45") (pin "5") (pinfunction "7_5") (pintype "output"))
    )
    (net (code "239") (name "~{CC_SDSQ}") (class "Default")
      (node (ref "E32") (pin "1") (pinfunction "I_1") (pintype "input"))
      (node (ref "E45") (pin "10") (pinfunction "3_10") (pintype "output"))
    )
    (net (code "240") (name "~{CC_SDSS}") (class "Default")
      (node (ref "E32") (pin "3") (pinfunction "I_3") (pintype "input"))
      (node (ref "E45") (pin "12") (pinfunction "1_12") (pintype "output"))
    )
    (net (code "241") (name "~{CC_SDST}") (class "Default")
      (node (ref "E32") (pin "5") (pinfunction "I_5") (pintype "input"))
      (node (ref "E45") (pin "11") (pinfunction "2_11") (pintype "output"))
    )
    (net (code "242") (name "~{CC_SETDLY}") (class "Default")
      (node (ref "E03") (pin "5") (pinfunction "Q_5") (pintype "output"))
      (node (ref "E22") (pin "4") (pinfunction "I0_4") (pintype "input"))
    )
    (net (code "243") (name "~{CC_TP3}") (class "Default")
      (node (ref "E01") (pin "1") (pinfunction "I_1") (pintype "input"))
      (node (ref "E02") (pin "2") (pinfunction "I0_2") (pintype "input"))
      (node (ref "E20") (pin "13") (pinfunction "O_13") (pintype "output"))
      (node (ref "E37") (pin "11") (pinfunction "I0_11") (pintype "input"))
    )
    (net (code "244") (name "~{CC_TPG1}") (class "Default")
      (node (ref "E14") (pin "6") (pinfunction "~{Q}_6") (pintype "output"))
      (node (ref "E42") (pin "1") (pinfunction "I0_1") (pintype "input"))
    )
    (net (code "245") (name "~{CC_TPG_CLK}") (class "Default")
      (node (ref "C40") (pin "1") (pinfunction "1_1") (pintype "passive"))
      (node (ref "E04") (pin "10") (pinfunction "B_10") (pintype "input"))
      (node (ref "R25") (pin "1") (pinfunction "1_1") (pintype "passive"))
    )
    (net (code "246") (name "~{CC_UNIT}") (class "Default")
      (node (ref "E05") (pin "11") (pinfunction "B2_11") (pintype "input"))
      (node (ref "E34") (pin "8") (pinfunction "~{Q}_8") (pintype "output"))
    )
    (net (code "247") (name "~{CC_UTS}") (class "Default")
      (node (ref "E02") (pin "11") (pinfunction "I0_11") (pintype "input"))
      (node (ref "E03") (pin "8") (pinfunction "~{Q}_8") (pintype "output"))
    )
    (net (code "248") (name "~{DF_HLD}") (class "Default")
      (node (ref "E10") (pin "11") (pinfunction "B2_11") (pintype "input"))
      (node (ref "E32") (pin "8") (pinfunction "O_8") (pintype "output"))
      (node (ref "E40") (pin "2") (pinfunction "I1_2") (pintype "input"))
    )
    (net (code "249") (name "~{DF_SEL_ER}") (class "Default")
      (node (ref "E32") (pin "13") (pinfunction "I_13") (pintype "input"))
      (node (ref "E40") (pin "5") (pinfunction "I4_5") (pintype "input"))
      (node (ref "Q2") (pin "3") (pinfunction "C_3") (pintype "passive"))
      (node (ref "Q3") (pin "3") (pinfunction "C_3") (pintype "passive"))
      (node (ref "R11") (pin "1") (pinfunction "1_1") (pintype "passive"))
    )
    (net (code "250") (name "~{DF_TIME_ER}") (class "Default")
      (node (ref "E27") (pin "12") (pinfunction "O_12") (pintype "output"))
      (node (ref "E35") (pin "5") (pinfunction "I2_5") (pintype "input"))
      (node (ref "E40") (pin "1") (pinfunction "I0_1") (pintype "input"))
    )
    (net (code "251") (name "~{MTR0}") (class "Default")
      (node (ref "E10") (pin "5") (pinfunction "B1_5") (pintype "input"))
      (node (ref "E29") (pin "7") (pinfunction "Q1_7") (pintype "output"))
    )
    (net (code "252") (name "~{MTR1}") (class "Default")
      (node (ref "E10") (pin "2") (pinfunction "B0_2") (pintype "input"))
      (node (ref "E29") (pin "5") (pinfunction "Q0_5") (pintype "output"))
    )
    (net (code "253") (name "~{MTR2}") (class "Default")
      (node (ref "E15") (pin "11") (pinfunction "B2_11") (pintype "input"))
      (node (ref "E21") (pin "11") (pinfunction "Q3_11") (pintype "output"))
      (node (ref "E29") (pin "4") (pinfunction "D_4") (pintype "input"))
    )
    (net (code "254") (name "~{MTR3}") (class "Default")
      (node (ref "E15") (pin "14") (pinfunction "B3_14") (pintype "input"))
      (node (ref "E21") (pin "9") (pinfunction "Q2_9") (pintype "output"))
    )
    (net (code "255") (name "~{MTR4}") (class "Default")
      (node (ref "E15") (pin "5") (pinfunction "B1_5") (pintype "input"))
      (node (ref "E21") (pin "7") (pinfunction "Q1_7") (pintype "output"))
    )
    (net (code "256") (name "~{MTR5}") (class "Default")
      (node (ref "E15") (pin "2") (pinfunction "B0_2") (pintype "input"))
      (node (ref "E21") (pin "5") (pinfunction "Q0_5") (pintype "output"))
    )
    (net (code "257") (name "~{POWER_OK}") (class "Default")
      (node (ref "E28") (pin "6") (pinfunction "I0_6") (pintype "input"))
      (node (ref "EDGE$") (pin "BV2") (pinfunction "1_BV2") (pintype "bidirectional"))
    )
    (net (code "258") (name "~{RTT}") (class "Default")
      (node (ref "E42") (pin "6") (pinfunction "I1_6") (pintype "input"))
      (node (ref "J1") (pin "J") (pinfunction "8_J") (pintype "bidirectional"))
      (node (ref "R18") (pin "1") (pinfunction "1_1") (pintype "passive"))
    )
    (net (code "259") (name "~{SKIP}") (class "Default")
      (node (ref "E41") (pin "1") (pinfunction "O_1") (pintype "open_collector"))
      (node (ref "E41") (pin "10") (pinfunction "O_10") (pintype "open_collector"))
      (node (ref "E41") (pin "13") (pinfunction "O_13") (pintype "open_collector"))
      (node (ref "EDGE$") (pin "CS1") (pinfunction "1_CS1") (pintype "bidirectional"))
    )
  )
)
